# protoplank.net
KiCad netlist of a schematic drawn in EAGLE
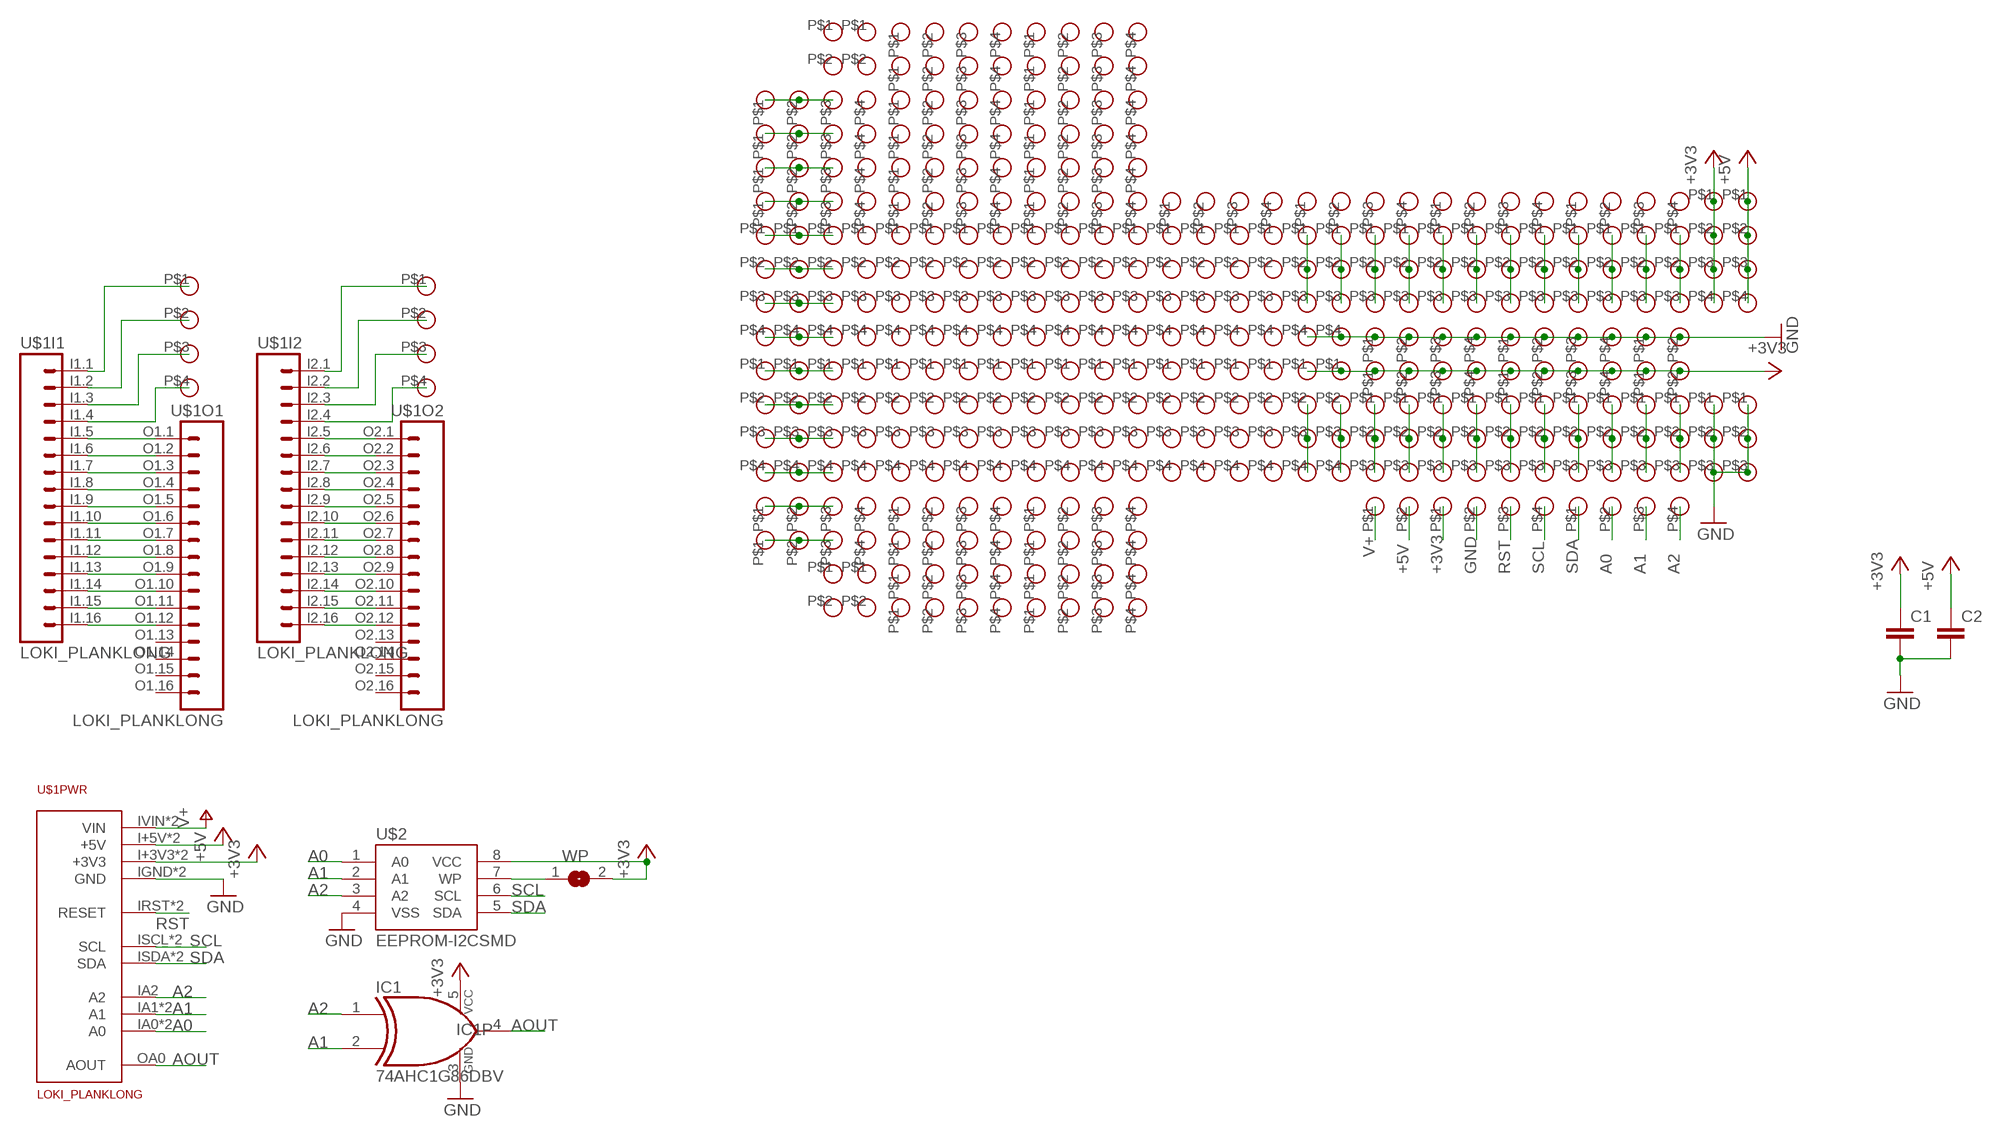
[diagram p0: schematic, sheet 1]

(export (version "E")
  (design (tool "Eeschema 10.0.6"))
  (components
    (comp (ref "C1")
      (value "CAPPTH")
      (footprint "eagle-import:CAP-PTH-SMALL")
      (libsource (lib "eagle-import") (part "CAPPTH"))
    )
    (comp (ref "C2")
      (value "CAPPTH")
      (footprint "eagle-import:CAP-PTH-SMALL")
      (libsource (lib "eagle-import") (part "CAPPTH"))
    )
    (comp (ref "IC1")
      (value "74AHC1G86DBV")
      (footprint "eagle-import:SOT23-5")
      (libsource (lib "eagle-import") (part "741G86DBVAHC"))
    )
    (comp (ref "U$1")
      (value "LOKI_PLANKLONG")
      (footprint "eagle-import:PLANK_LONG")
      (libsource (lib "eagle-import") (part "LOKI_PLANKLONG"))
    )
    (comp (ref "U$2")
      (value "EEPROM-I2CSMD")
      (footprint "eagle-import:SO08")
      (libsource (lib "eagle-import") (part "EEPROM-I2CSMD"))
    )
    (comp (ref "U$3")
      (value "PROTOPAD-3")
      (footprint "eagle-import:PROTOPAD-3")
      (libsource (lib "eagle-import") (part "PROTOPAD-3"))
    )
    (comp (ref "U$4")
      (value "PROTOPAD-3")
      (footprint "eagle-import:PROTOPAD-3")
      (libsource (lib "eagle-import") (part "PROTOPAD-3"))
    )
    (comp (ref "U$5")
      (value "PROTOPAD-3")
      (footprint "eagle-import:PROTOPAD-3")
      (libsource (lib "eagle-import") (part "PROTOPAD-3"))
    )
    (comp (ref "U$6")
      (value "PROTOPAD-3")
      (footprint "eagle-import:PROTOPAD-3")
      (libsource (lib "eagle-import") (part "PROTOPAD-3"))
    )
    (comp (ref "U$7")
      (value "PROTOPAD-3")
      (footprint "eagle-import:PROTOPAD-3")
      (libsource (lib "eagle-import") (part "PROTOPAD-3"))
    )
    (comp (ref "U$8")
      (value "PROTOPAD-3")
      (footprint "eagle-import:PROTOPAD-3")
      (libsource (lib "eagle-import") (part "PROTOPAD-3"))
    )
    (comp (ref "U$9")
      (value "PROTOPAD-3")
      (footprint "eagle-import:PROTOPAD-3")
      (libsource (lib "eagle-import") (part "PROTOPAD-3"))
    )
    (comp (ref "U$10")
      (value "PROTOPAD-3")
      (footprint "eagle-import:PROTOPAD-3")
      (libsource (lib "eagle-import") (part "PROTOPAD-3"))
    )
    (comp (ref "U$11")
      (value "PROTOPAD-3")
      (footprint "eagle-import:PROTOPAD-3")
      (libsource (lib "eagle-import") (part "PROTOPAD-3"))
    )
    (comp (ref "U$12")
      (value "PROTOPAD-3")
      (footprint "eagle-import:PROTOPAD-3")
      (libsource (lib "eagle-import") (part "PROTOPAD-3"))
    )
    (comp (ref "U$13")
      (value "PROTOPAD-3")
      (footprint "eagle-import:PROTOPAD-3")
      (libsource (lib "eagle-import") (part "PROTOPAD-3"))
    )
    (comp (ref "U$14")
      (value "PROTOPAD-3")
      (footprint "eagle-import:PROTOPAD-3")
      (libsource (lib "eagle-import") (part "PROTOPAD-3"))
    )
    (comp (ref "U$15")
      (value "PROTOPAD-3")
      (footprint "eagle-import:PROTOPAD-3")
      (libsource (lib "eagle-import") (part "PROTOPAD-3"))
    )
    (comp (ref "U$16")
      (value "PROTOPAD-3")
      (footprint "eagle-import:PROTOPAD-3")
      (libsource (lib "eagle-import") (part "PROTOPAD-3"))
    )
    (comp (ref "U$17")
      (value "PROTOPAD-3")
      (footprint "eagle-import:PROTOPAD-3")
      (libsource (lib "eagle-import") (part "PROTOPAD-3"))
    )
    (comp (ref "U$18")
      (value "PROTOPAD-3")
      (footprint "eagle-import:PROTOPAD-3")
      (libsource (lib "eagle-import") (part "PROTOPAD-3"))
    )
    (comp (ref "U$19")
      (value "PROTOPAD-3")
      (footprint "eagle-import:PROTOPAD-3")
      (libsource (lib "eagle-import") (part "PROTOPAD-3"))
    )
    (comp (ref "U$20")
      (value "PROTOPAD-3")
      (footprint "eagle-import:PROTOPAD-3")
      (libsource (lib "eagle-import") (part "PROTOPAD-3"))
    )
    (comp (ref "U$21")
      (value "PROTOPAD-3")
      (footprint "eagle-import:PROTOPAD-3")
      (libsource (lib "eagle-import") (part "PROTOPAD-3"))
    )
    (comp (ref "U$22")
      (value "PROTOPAD-3")
      (footprint "eagle-import:PROTOPAD-3")
      (libsource (lib "eagle-import") (part "PROTOPAD-3"))
    )
    (comp (ref "U$23")
      (value "PROTOPAD-4SQUARE")
      (footprint "eagle-import:PROTOPAD-4")
      (libsource (lib "eagle-import") (part "PROTOPAD-4SQUARE"))
    )
    (comp (ref "U$24")
      (value "PROTOPAD-4SQUARE")
      (footprint "eagle-import:PROTOPAD-4")
      (libsource (lib "eagle-import") (part "PROTOPAD-4SQUARE"))
    )
    (comp (ref "U$25")
      (value "PROTOPAD-4SQUARE")
      (footprint "eagle-import:PROTOPAD-4")
      (libsource (lib "eagle-import") (part "PROTOPAD-4SQUARE"))
    )
    (comp (ref "U$26")
      (value "PROTOPAD-4SQUARE")
      (footprint "eagle-import:PROTOPAD-4")
      (libsource (lib "eagle-import") (part "PROTOPAD-4SQUARE"))
    )
    (comp (ref "U$27")
      (value "PROTOPAD-2SQUARE")
      (footprint "eagle-import:PROTOPAD-2")
      (libsource (lib "eagle-import") (part "PROTOPAD-2SQUARE"))
    )
    (comp (ref "U$28")
      (value "PROTOPAD-2SQUARE")
      (footprint "eagle-import:PROTOPAD-2")
      (libsource (lib "eagle-import") (part "PROTOPAD-2SQUARE"))
    )
    (comp (ref "U$29")
      (value "PROTOPAD-4ROUND")
      (footprint "eagle-import:PROTOPAD-4-ROUND")
      (libsource (lib "eagle-import") (part "PROTOPAD-4ROUND"))
    )
    (comp (ref "U$30")
      (value "PROTOPAD-4ROUND")
      (footprint "eagle-import:PROTOPAD-4-ROUND")
      (libsource (lib "eagle-import") (part "PROTOPAD-4ROUND"))
    )
    (comp (ref "U$31")
      (value "PROTOPAD-4ROUND")
      (footprint "eagle-import:PROTOPAD-4-ROUND")
      (libsource (lib "eagle-import") (part "PROTOPAD-4ROUND"))
    )
    (comp (ref "U$32")
      (value "PROTOPAD-4ROUND")
      (footprint "eagle-import:PROTOPAD-4-ROUND")
      (libsource (lib "eagle-import") (part "PROTOPAD-4ROUND"))
    )
    (comp (ref "U$33")
      (value "PROTOPAD-2ROUND")
      (footprint "eagle-import:PROTOPAD-2-ROUND")
      (libsource (lib "eagle-import") (part "PROTOPAD-2ROUND"))
    )
    (comp (ref "U$34")
      (value "PROTOPAD-4SQUARE")
      (footprint "eagle-import:PROTOPAD-4")
      (libsource (lib "eagle-import") (part "PROTOPAD-4SQUARE"))
    )
    (comp (ref "U$35")
      (value "PROTOPAD-4SQUARE")
      (footprint "eagle-import:PROTOPAD-4")
      (libsource (lib "eagle-import") (part "PROTOPAD-4SQUARE"))
    )
    (comp (ref "U$36")
      (value "PROTOPAD-4SQUARE")
      (footprint "eagle-import:PROTOPAD-4")
      (libsource (lib "eagle-import") (part "PROTOPAD-4SQUARE"))
    )
    (comp (ref "U$37")
      (value "PROTOPAD-4SQUARE")
      (footprint "eagle-import:PROTOPAD-4")
      (libsource (lib "eagle-import") (part "PROTOPAD-4SQUARE"))
    )
    (comp (ref "U$38")
      (value "PROTOPAD-4SQUARE")
      (footprint "eagle-import:PROTOPAD-4")
      (libsource (lib "eagle-import") (part "PROTOPAD-4SQUARE"))
    )
    (comp (ref "U$39")
      (value "PROTOPAD-4SQUARE")
      (footprint "eagle-import:PROTOPAD-4")
      (libsource (lib "eagle-import") (part "PROTOPAD-4SQUARE"))
    )
    (comp (ref "U$40")
      (value "PROTOPAD-4SQUARE")
      (footprint "eagle-import:PROTOPAD-4")
      (libsource (lib "eagle-import") (part "PROTOPAD-4SQUARE"))
    )
    (comp (ref "U$41")
      (value "PROTOPAD-4SQUARE")
      (footprint "eagle-import:PROTOPAD-4")
      (libsource (lib "eagle-import") (part "PROTOPAD-4SQUARE"))
    )
    (comp (ref "U$42")
      (value "PROTOPAD-4SQUARE")
      (footprint "eagle-import:PROTOPAD-4")
      (libsource (lib "eagle-import") (part "PROTOPAD-4SQUARE"))
    )
    (comp (ref "U$43")
      (value "PROTOPAD-4SQUARE")
      (footprint "eagle-import:PROTOPAD-4")
      (libsource (lib "eagle-import") (part "PROTOPAD-4SQUARE"))
    )
    (comp (ref "U$44")
      (value "PROTOPAD-4SQUARE")
      (footprint "eagle-import:PROTOPAD-4")
      (libsource (lib "eagle-import") (part "PROTOPAD-4SQUARE"))
    )
    (comp (ref "U$45")
      (value "PROTOPAD-4SQUARE")
      (footprint "eagle-import:PROTOPAD-4")
      (libsource (lib "eagle-import") (part "PROTOPAD-4SQUARE"))
    )
    (comp (ref "U$46")
      (value "PROTOPAD-4SQUARE")
      (footprint "eagle-import:PROTOPAD-4")
      (libsource (lib "eagle-import") (part "PROTOPAD-4SQUARE"))
    )
    (comp (ref "U$47")
      (value "PROTOPAD-4SQUARE")
      (footprint "eagle-import:PROTOPAD-4")
      (libsource (lib "eagle-import") (part "PROTOPAD-4SQUARE"))
    )
    (comp (ref "U$48")
      (value "PROTOPAD-4SQUARE")
      (footprint "eagle-import:PROTOPAD-4")
      (libsource (lib "eagle-import") (part "PROTOPAD-4SQUARE"))
    )
    (comp (ref "U$49")
      (value "PROTOPAD-4SQUARE")
      (footprint "eagle-import:PROTOPAD-4")
      (libsource (lib "eagle-import") (part "PROTOPAD-4SQUARE"))
    )
    (comp (ref "U$50")
      (value "PROTOPAD-4SQUARE")
      (footprint "eagle-import:PROTOPAD-4")
      (libsource (lib "eagle-import") (part "PROTOPAD-4SQUARE"))
    )
    (comp (ref "U$51")
      (value "PROTOPAD-4SQUARE")
      (footprint "eagle-import:PROTOPAD-4")
      (libsource (lib "eagle-import") (part "PROTOPAD-4SQUARE"))
    )
    (comp (ref "U$52")
      (value "PROTOPAD-4SQUARE")
      (footprint "eagle-import:PROTOPAD-4")
      (libsource (lib "eagle-import") (part "PROTOPAD-4SQUARE"))
    )
    (comp (ref "U$53")
      (value "PROTOPAD-4SQUARE")
      (footprint "eagle-import:PROTOPAD-4")
      (libsource (lib "eagle-import") (part "PROTOPAD-4SQUARE"))
    )
    (comp (ref "U$54")
      (value "PROTOPAD-4SQUARE")
      (footprint "eagle-import:PROTOPAD-4")
      (libsource (lib "eagle-import") (part "PROTOPAD-4SQUARE"))
    )
    (comp (ref "U$55")
      (value "PROTOPAD-4SQUARE")
      (footprint "eagle-import:PROTOPAD-4")
      (libsource (lib "eagle-import") (part "PROTOPAD-4SQUARE"))
    )
    (comp (ref "U$56")
      (value "PROTOPAD-4SQUARE")
      (footprint "eagle-import:PROTOPAD-4")
      (libsource (lib "eagle-import") (part "PROTOPAD-4SQUARE"))
    )
    (comp (ref "U$57")
      (value "PROTOPAD-4SQUARE")
      (footprint "eagle-import:PROTOPAD-4")
      (libsource (lib "eagle-import") (part "PROTOPAD-4SQUARE"))
    )
    (comp (ref "U$58")
      (value "PROTOPAD-4SQUARE")
      (footprint "eagle-import:PROTOPAD-4")
      (libsource (lib "eagle-import") (part "PROTOPAD-4SQUARE"))
    )
    (comp (ref "U$59")
      (value "PROTOPAD-4SQUARE")
      (footprint "eagle-import:PROTOPAD-4")
      (libsource (lib "eagle-import") (part "PROTOPAD-4SQUARE"))
    )
    (comp (ref "U$60")
      (value "PROTOPAD-4SQUARE")
      (footprint "eagle-import:PROTOPAD-4")
      (libsource (lib "eagle-import") (part "PROTOPAD-4SQUARE"))
    )
    (comp (ref "U$61")
      (value "PROTOPAD-4SQUARE")
      (footprint "eagle-import:PROTOPAD-4")
      (libsource (lib "eagle-import") (part "PROTOPAD-4SQUARE"))
    )
    (comp (ref "U$62")
      (value "PROTOPAD-4SQUARE")
      (footprint "eagle-import:PROTOPAD-4")
      (libsource (lib "eagle-import") (part "PROTOPAD-4SQUARE"))
    )
    (comp (ref "U$63")
      (value "PROTOPAD-4SQUARE")
      (footprint "eagle-import:PROTOPAD-4")
      (libsource (lib "eagle-import") (part "PROTOPAD-4SQUARE"))
    )
    (comp (ref "U$64")
      (value "PROTOPAD-4SQUARE")
      (footprint "eagle-import:PROTOPAD-4")
      (libsource (lib "eagle-import") (part "PROTOPAD-4SQUARE"))
    )
    (comp (ref "U$65")
      (value "PROTOPAD-4SQUARE")
      (footprint "eagle-import:PROTOPAD-4")
      (libsource (lib "eagle-import") (part "PROTOPAD-4SQUARE"))
    )
    (comp (ref "U$66")
      (value "PROTOPAD-4SQUARE")
      (footprint "eagle-import:PROTOPAD-4")
      (libsource (lib "eagle-import") (part "PROTOPAD-4SQUARE"))
    )
    (comp (ref "U$67")
      (value "PROTOPAD-4SQUARE")
      (footprint "eagle-import:PROTOPAD-4")
      (libsource (lib "eagle-import") (part "PROTOPAD-4SQUARE"))
    )
    (comp (ref "U$68")
      (value "PROTOPAD-4SQUARE")
      (footprint "eagle-import:PROTOPAD-4")
      (libsource (lib "eagle-import") (part "PROTOPAD-4SQUARE"))
    )
    (comp (ref "U$69")
      (value "PROTOPAD-4SQUARE")
      (footprint "eagle-import:PROTOPAD-4")
      (libsource (lib "eagle-import") (part "PROTOPAD-4SQUARE"))
    )
    (comp (ref "U$70")
      (value "PROTOPAD-4SQUARE")
      (footprint "eagle-import:PROTOPAD-4")
      (libsource (lib "eagle-import") (part "PROTOPAD-4SQUARE"))
    )
    (comp (ref "U$71")
      (value "PROTOPAD-4SQUARE")
      (footprint "eagle-import:PROTOPAD-4")
      (libsource (lib "eagle-import") (part "PROTOPAD-4SQUARE"))
    )
    (comp (ref "U$72")
      (value "PROTOPAD-4SQUARE")
      (footprint "eagle-import:PROTOPAD-4")
      (libsource (lib "eagle-import") (part "PROTOPAD-4SQUARE"))
    )
    (comp (ref "U$73")
      (value "PROTOPAD-4SQUARE")
      (footprint "eagle-import:PROTOPAD-4")
      (libsource (lib "eagle-import") (part "PROTOPAD-4SQUARE"))
    )
    (comp (ref "U$74")
      (value "PROTOPAD-4SQUARE")
      (footprint "eagle-import:PROTOPAD-4")
      (libsource (lib "eagle-import") (part "PROTOPAD-4SQUARE"))
    )
    (comp (ref "U$75")
      (value "PROTOPAD-4SQUARE")
      (footprint "eagle-import:PROTOPAD-4")
      (libsource (lib "eagle-import") (part "PROTOPAD-4SQUARE"))
    )
    (comp (ref "U$76")
      (value "PROTOPAD-4SQUARE")
      (footprint "eagle-import:PROTOPAD-4")
      (libsource (lib "eagle-import") (part "PROTOPAD-4SQUARE"))
    )
    (comp (ref "U$77")
      (value "PROTOPAD-4SQUARE")
      (footprint "eagle-import:PROTOPAD-4")
      (libsource (lib "eagle-import") (part "PROTOPAD-4SQUARE"))
    )
    (comp (ref "U$78")
      (value "PROTOPAD-3")
      (footprint "eagle-import:PROTOPAD-3")
      (libsource (lib "eagle-import") (part "PROTOPAD-3"))
    )
    (comp (ref "U$79")
      (value "PROTOPAD-4SQUARE")
      (footprint "eagle-import:PROTOPAD-4")
      (libsource (lib "eagle-import") (part "PROTOPAD-4SQUARE"))
    )
    (comp (ref "U$80")
      (value "PROTOPAD-3")
      (footprint "eagle-import:PROTOPAD-3")
      (libsource (lib "eagle-import") (part "PROTOPAD-3"))
    )
    (comp (ref "U$81")
      (value "PROTOPAD-4SQUARE")
      (footprint "eagle-import:PROTOPAD-4")
      (libsource (lib "eagle-import") (part "PROTOPAD-4SQUARE"))
    )
    (comp (ref "U$82")
      (value "PROTOPAD-4SQUARE")
      (footprint "eagle-import:PROTOPAD-4")
      (libsource (lib "eagle-import") (part "PROTOPAD-4SQUARE"))
    )
    (comp (ref "U$83")
      (value "PROTOPAD-4SQUARE")
      (footprint "eagle-import:PROTOPAD-4")
      (libsource (lib "eagle-import") (part "PROTOPAD-4SQUARE"))
    )
    (comp (ref "U$84")
      (value "PROTOPAD-4SQUARE")
      (footprint "eagle-import:PROTOPAD-4")
      (libsource (lib "eagle-import") (part "PROTOPAD-4SQUARE"))
    )
    (comp (ref "U$85")
      (value "PROTOPAD-4SQUARE")
      (footprint "eagle-import:PROTOPAD-4")
      (libsource (lib "eagle-import") (part "PROTOPAD-4SQUARE"))
    )
    (comp (ref "U$86")
      (value "PROTOPAD-4SQUARE")
      (footprint "eagle-import:PROTOPAD-4")
      (libsource (lib "eagle-import") (part "PROTOPAD-4SQUARE"))
    )
    (comp (ref "U$87")
      (value "PROTOPAD-4SQUARE")
      (footprint "eagle-import:PROTOPAD-4")
      (libsource (lib "eagle-import") (part "PROTOPAD-4SQUARE"))
    )
    (comp (ref "U$88")
      (value "PROTOPAD-4SQUARE")
      (footprint "eagle-import:PROTOPAD-4")
      (libsource (lib "eagle-import") (part "PROTOPAD-4SQUARE"))
    )
    (comp (ref "U$89")
      (value "PROTOPAD-4SQUARE")
      (footprint "eagle-import:PROTOPAD-4")
      (libsource (lib "eagle-import") (part "PROTOPAD-4SQUARE"))
    )
    (comp (ref "U$90")
      (value "PROTOPAD-4SQUARE")
      (footprint "eagle-import:PROTOPAD-4")
      (libsource (lib "eagle-import") (part "PROTOPAD-4SQUARE"))
    )
    (comp (ref "U$91")
      (value "PROTOPAD-4SQUARE")
      (footprint "eagle-import:PROTOPAD-4")
      (libsource (lib "eagle-import") (part "PROTOPAD-4SQUARE"))
    )
    (comp (ref "U$92")
      (value "PROTOPAD-4SQUARE")
      (footprint "eagle-import:PROTOPAD-4")
      (libsource (lib "eagle-import") (part "PROTOPAD-4SQUARE"))
    )
    (comp (ref "U$93")
      (value "PROTOPAD-4SQUARE")
      (footprint "eagle-import:PROTOPAD-4")
      (libsource (lib "eagle-import") (part "PROTOPAD-4SQUARE"))
    )
    (comp (ref "U$94")
      (value "PROTOPAD-4SQUARE")
      (footprint "eagle-import:PROTOPAD-4")
      (libsource (lib "eagle-import") (part "PROTOPAD-4SQUARE"))
    )
    (comp (ref "U$95")
      (value "PROTOPAD-4SQUARE")
      (footprint "eagle-import:PROTOPAD-4")
      (libsource (lib "eagle-import") (part "PROTOPAD-4SQUARE"))
    )
    (comp (ref "U$96")
      (value "PROTOPAD-4SQUARE")
      (footprint "eagle-import:PROTOPAD-4")
      (libsource (lib "eagle-import") (part "PROTOPAD-4SQUARE"))
    )
    (comp (ref "U$97")
      (value "PROTOPAD-4SQUARE")
      (footprint "eagle-import:PROTOPAD-4")
      (libsource (lib "eagle-import") (part "PROTOPAD-4SQUARE"))
    )
    (comp (ref "U$98")
      (value "PROTOPAD-4SQUARE")
      (footprint "eagle-import:PROTOPAD-4")
      (libsource (lib "eagle-import") (part "PROTOPAD-4SQUARE"))
    )
    (comp (ref "U$99")
      (value "PROTOPAD-4SQUARE")
      (footprint "eagle-import:PROTOPAD-4")
      (libsource (lib "eagle-import") (part "PROTOPAD-4SQUARE"))
    )
    (comp (ref "U$100")
      (value "PROTOPAD-4SQUARE")
      (footprint "eagle-import:PROTOPAD-4")
      (libsource (lib "eagle-import") (part "PROTOPAD-4SQUARE"))
    )
    (comp (ref "U$101")
      (value "PROTOPAD-4SQUARE")
      (footprint "eagle-import:PROTOPAD-4")
      (libsource (lib "eagle-import") (part "PROTOPAD-4SQUARE"))
    )
    (comp (ref "U$102")
      (value "PROTOPAD-4SQUARE")
      (footprint "eagle-import:PROTOPAD-4")
      (libsource (lib "eagle-import") (part "PROTOPAD-4SQUARE"))
    )
    (comp (ref "U$103")
      (value "PROTOPAD-4SQUARE")
      (footprint "eagle-import:PROTOPAD-4")
      (libsource (lib "eagle-import") (part "PROTOPAD-4SQUARE"))
    )
    (comp (ref "U$104")
      (value "PROTOPAD-2SQUARE")
      (footprint "eagle-import:PROTOPAD-2")
      (libsource (lib "eagle-import") (part "PROTOPAD-2SQUARE"))
    )
    (comp (ref "U$105")
      (value "PROTOPAD-2SQUARE")
      (footprint "eagle-import:PROTOPAD-2")
      (libsource (lib "eagle-import") (part "PROTOPAD-2SQUARE"))
    )
    (comp (ref "U$106")
      (value "PROTOPAD-2SQUARE")
      (footprint "eagle-import:PROTOPAD-2")
      (libsource (lib "eagle-import") (part "PROTOPAD-2SQUARE"))
    )
    (comp (ref "U$107")
      (value "PROTOPAD-2SQUARE")
      (footprint "eagle-import:PROTOPAD-2")
      (libsource (lib "eagle-import") (part "PROTOPAD-2SQUARE"))
    )
    (comp (ref "WP") (value "SJ") (footprint "eagle-import:SJ") (libsource (lib "eagle-import") (part "SJ")))
  )
  (nets
    (net (code "1") (name "+3V3") (class "Default")
      (node (ref "C1") (pin "1") (pinfunction "1_1") (pintype "passive"))
      (node (ref "IC1") (pin "5") (pinfunction "VCC_5") (pintype "power_in"))
      (node (ref "U$1") (pin "I+3V3") (pinfunction "+3V3_I+3V3") (pintype "power_in"))
      (node (ref "U$1") (pin "O+3V3") (pinfunction "+3V3_O+3V3") (pintype "power_in"))
      (node (ref "U$2") (pin "8") (pinfunction "VCC_8") (pintype "power_in"))
      (node (ref "U$25") (pin "P$1") (pinfunction "P$1_P$1") (pintype "passive"))
      (node (ref "U$25") (pin "P$2") (pinfunction "P$2_P$2") (pintype "passive"))
      (node (ref "U$25") (pin "P$3") (pinfunction "P$3_P$3") (pintype "passive"))
      (node (ref "U$25") (pin "P$4") (pinfunction "P$4_P$4") (pintype "passive"))
      (node (ref "U$26") (pin "P$1") (pinfunction "P$1_P$1") (pintype "passive"))
      (node (ref "U$26") (pin "P$2") (pinfunction "P$2_P$2") (pintype "passive"))
      (node (ref "U$26") (pin "P$3") (pinfunction "P$3_P$3") (pintype "passive"))
      (node (ref "U$26") (pin "P$4") (pinfunction "P$4_P$4") (pintype "passive"))
      (node (ref "U$28") (pin "P$1") (pinfunction "P$1_P$1") (pintype "passive"))
      (node (ref "U$28") (pin "P$2") (pinfunction "P$2_P$2") (pintype "passive"))
      (node (ref "U$32") (pin "P$1") (pinfunction "P$1_P$1") (pintype "passive"))
      (node (ref "U$35") (pin "P$1") (pinfunction "P$1_P$1") (pintype "passive"))
      (node (ref "U$36") (pin "P$1") (pinfunction "P$1_P$1") (pintype "passive"))
      (node (ref "U$77") (pin "P$1") (pinfunction "P$1_P$1") (pintype "passive"))
      (node (ref "U$77") (pin "P$2") (pinfunction "P$2_P$2") (pintype "passive"))
      (node (ref "U$77") (pin "P$3") (pinfunction "P$3_P$3") (pintype "passive"))
      (node (ref "U$77") (pin "P$4") (pinfunction "P$4_P$4") (pintype "passive"))
      (node (ref "WP") (pin "2") (pinfunction "2_2") (pintype "passive"))
    )
    (net (code "2") (name "+5V") (class "Default")
      (node (ref "C2") (pin "1") (pinfunction "1_1") (pintype "passive"))
      (node (ref "U$1") (pin "I+5V") (pinfunction "+5V_I+5V") (pintype "power_in"))
      (node (ref "U$1") (pin "O+5V") (pinfunction "+5V_O+5V") (pintype "power_in"))
      (node (ref "U$33") (pin "P$2") (pinfunction "P$2_P$2") (pintype "passive"))
      (node (ref "U$79") (pin "P$1") (pinfunction "P$1_P$1") (pintype "passive"))
      (node (ref "U$79") (pin "P$2") (pinfunction "P$2_P$2") (pintype "passive"))
      (node (ref "U$79") (pin "P$3") (pinfunction "P$3_P$3") (pintype "passive"))
      (node (ref "U$79") (pin "P$4") (pinfunction "P$4_P$4") (pintype "passive"))
    )
    (net (code "3") (name "/A0") (class "Default")
      (node (ref "U$1") (pin "IA0") (pinfunction "A0_IA0") (pintype "output"))
      (node (ref "U$1") (pin "OA1") (pinfunction "A0_OA1") (pintype "output"))
      (node (ref "U$2") (pin "1") (pinfunction "A0_1") (pintype "bidirectional"))
      (node (ref "U$31") (pin "P$2") (pinfunction "P$2_P$2") (pintype "passive"))
    )
    (net (code "4") (name "/A1") (class "Default")
      (node (ref "IC1") (pin "2") (pinfunction "I1_2") (pintype "input"))
      (node (ref "U$1") (pin "IA1") (pinfunction "A1_IA1") (pintype "output"))
      (node (ref "U$1") (pin "OA2") (pinfunction "A1_OA2") (pintype "output"))
      (node (ref "U$2") (pin "2") (pinfunction "A1_2") (pintype "bidirectional"))
      (node (ref "U$31") (pin "P$3") (pinfunction "P$3_P$3") (pintype "passive"))
    )
    (net (code "5") (name "/A2") (class "Default")
      (node (ref "IC1") (pin "1") (pinfunction "I0_1") (pintype "input"))
      (node (ref "U$1") (pin "IA2") (pinfunction "A2_IA2") (pintype "output"))
      (node (ref "U$2") (pin "3") (pinfunction "A2_3") (pintype "bidirectional"))
      (node (ref "U$31") (pin "P$4") (pinfunction "P$4_P$4") (pintype "passive"))
    )
    (net (code "6") (name "/AOUT") (class "Default")
      (node (ref "IC1") (pin "4") (pinfunction "O_4") (pintype "output"))
      (node (ref "U$1") (pin "OA0") (pinfunction "AOUT_OA0") (pintype "input"))
    )
    (net (code "7") (name "/RST") (class "Default")
      (node (ref "U$1") (pin "IRST") (pinfunction "RESET_IRST") (pintype "input"))
      (node (ref "U$1") (pin "ORST") (pinfunction "RESET_ORST") (pintype "input"))
      (node (ref "U$32") (pin "P$3") (pinfunction "P$3_P$3") (pintype "passive"))
    )
    (net (code "8") (name "/SCL") (class "Default")
      (node (ref "U$1") (pin "ISCL") (pinfunction "SCL_ISCL") (pintype "bidirectional"))
      (node (ref "U$1") (pin "OSCL") (pinfunction "SCL_OSCL") (pintype "bidirectional"))
      (node (ref "U$2") (pin "6") (pinfunction "SCL_6") (pintype "bidirectional"))
      (node (ref "U$32") (pin "P$4") (pinfunction "P$4_P$4") (pintype "passive"))
    )
    (net (code "9") (name "/SDA") (class "Default")
      (node (ref "U$1") (pin "ISDA") (pinfunction "SDA_ISDA") (pintype "bidirectional"))
      (node (ref "U$1") (pin "OSDA") (pinfunction "SDA_OSDA") (pintype "bidirectional"))
      (node (ref "U$2") (pin "5") (pinfunction "SDA_5") (pintype "bidirectional"))
      (node (ref "U$31") (pin "P$1") (pinfunction "P$1_P$1") (pintype "passive"))
    )
    (net (code "10") (name "GND") (class "Default")
      (node (ref "C1") (pin "2") (pinfunction "2_2") (pintype "passive"))
      (node (ref "C2") (pin "2") (pinfunction "2_2") (pintype "passive"))
      (node (ref "IC1") (pin "3") (pinfunction "GND_3") (pintype "power_in"))
      (node (ref "U$1") (pin "IGND") (pinfunction "GND_IGND") (pintype "power_in"))
      (node (ref "U$1") (pin "OGND") (pinfunction "GND_OGND") (pintype "power_in"))
      (node (ref "U$2") (pin "4") (pinfunction "VSS_4") (pintype "power_in"))
      (node (ref "U$23") (pin "P$1") (pinfunction "P$1_P$1") (pintype "passive"))
      (node (ref "U$23") (pin "P$2") (pinfunction "P$2_P$2") (pintype "passive"))
      (node (ref "U$23") (pin "P$3") (pinfunction "P$3_P$3") (pintype "passive"))
      (node (ref "U$23") (pin "P$4") (pinfunction "P$4_P$4") (pintype "passive"))
      (node (ref "U$24") (pin "P$1") (pinfunction "P$1_P$1") (pintype "passive"))
      (node (ref "U$24") (pin "P$2") (pinfunction "P$2_P$2") (pintype "passive"))
      (node (ref "U$24") (pin "P$3") (pinfunction "P$3_P$3") (pintype "passive"))
      (node (ref "U$24") (pin "P$4") (pinfunction "P$4_P$4") (pintype "passive"))
      (node (ref "U$27") (pin "P$1") (pinfunction "P$1_P$1") (pintype "passive"))
      (node (ref "U$27") (pin "P$2") (pinfunction "P$2_P$2") (pintype "passive"))
      (node (ref "U$32") (pin "P$2") (pinfunction "P$2_P$2") (pintype "passive"))
      (node (ref "U$34") (pin "P$4") (pinfunction "P$4_P$4") (pintype "passive"))
      (node (ref "U$37") (pin "P$4") (pinfunction "P$4_P$4") (pintype "passive"))
      (node (ref "U$78") (pin "P$1") (pinfunction "P$1_P$1") (pintype "passive"))
      (node (ref "U$78") (pin "P$2") (pinfunction "P$2_P$2") (pintype "passive"))
      (node (ref "U$78") (pin "P$3") (pinfunction "P$3_P$3") (pintype "passive"))
      (node (ref "U$80") (pin "P$1") (pinfunction "P$1_P$1") (pintype "passive"))
      (node (ref "U$80") (pin "P$2") (pinfunction "P$2_P$2") (pintype "passive"))
      (node (ref "U$80") (pin "P$3") (pinfunction "P$3_P$3") (pintype "passive"))
    )
    (net (code "11") (name "Net-(U$1A-1)") (class "Default")
      (node (ref "U$1") (pin "I1.1") (pinfunction "1_I1.1") (pintype "passive"))
      (node (ref "U$29") (pin "P$1") (pinfunction "P$1_P$1") (pintype "passive"))
    )
    (net (code "12") (name "Net-(U$1A-2)") (class "Default")
      (node (ref "U$1") (pin "I1.2") (pinfunction "2_I1.2") (pintype "passive"))
      (node (ref "U$29") (pin "P$2") (pinfunction "P$2_P$2") (pintype "passive"))
    )
    (net (code "13") (name "Net-(U$1A-3)") (class "Default")
      (node (ref "U$1") (pin "I1.3") (pinfunction "3_I1.3") (pintype "passive"))
      (node (ref "U$29") (pin "P$3") (pinfunction "P$3_P$3") (pintype "passive"))
    )
    (net (code "14") (name "Net-(U$1A-4)") (class "Default")
      (node (ref "U$1") (pin "I1.4") (pinfunction "4_I1.4") (pintype "passive"))
      (node (ref "U$29") (pin "P$4") (pinfunction "P$4_P$4") (pintype "passive"))
    )
    (net (code "15") (name "Net-(U$1A-5)") (class "Default")
      (node (ref "U$1") (pin "I1.5") (pinfunction "5_I1.5") (pintype "passive"))
      (node (ref "U$1") (pin "O1.1") (pinfunction "1_O1.1") (pintype "passive"))
    )
    (net (code "16") (name "Net-(U$1A-6)") (class "Default")
      (node (ref "U$1") (pin "I1.6") (pinfunction "6_I1.6") (pintype "passive"))
      (node (ref "U$1") (pin "O1.2") (pinfunction "2_O1.2") (pintype "passive"))
    )
    (net (code "17") (name "Net-(U$1A-7)") (class "Default")
      (node (ref "U$1") (pin "I1.7") (pinfunction "7_I1.7") (pintype "passive"))
      (node (ref "U$1") (pin "O1.3") (pinfunction "3_O1.3") (pintype "passive"))
    )
    (net (code "18") (name "Net-(U$1A-8)") (class "Default")
      (node (ref "U$1") (pin "I1.8") (pinfunction "8_I1.8") (pintype "passive"))
      (node (ref "U$1") (pin "O1.4") (pinfunction "4_O1.4") (pintype "passive"))
    )
    (net (code "19") (name "Net-(U$1A-9)") (class "Default")
      (node (ref "U$1") (pin "I1.9") (pinfunction "9_I1.9") (pintype "passive"))
      (node (ref "U$1") (pin "O1.5") (pinfunction "5_O1.5") (pintype "passive"))
    )
    (net (code "20") (name "Net-(U$1A-10)") (class "Default")
      (node (ref "U$1") (pin "I1.10") (pinfunction "10_I1.10") (pintype "passive"))
      (node (ref "U$1") (pin "O1.6") (pinfunction "6_O1.6") (pintype "passive"))
    )
    (net (code "21") (name "Net-(U$1A-11)") (class "Default")
      (node (ref "U$1") (pin "I1.11") (pinfunction "11_I1.11") (pintype "passive"))
      (node (ref "U$1") (pin "O1.7") (pinfunction "7_O1.7") (pintype "passive"))
    )
    (net (code "22") (name "Net-(U$1A-12)") (class "Default")
      (node (ref "U$1") (pin "I1.12") (pinfunction "12_I1.12") (pintype "passive"))
      (node (ref "U$1") (pin "O1.8") (pinfunction "8_O1.8") (pintype "passive"))
    )
    (net (code "23") (name "Net-(U$1A-13)") (class "Default")
      (node (ref "U$1") (pin "I1.13") (pinfunction "13_I1.13") (pintype "passive"))
      (node (ref "U$1") (pin "O1.9") (pinfunction "9_O1.9") (pintype "passive"))
    )
    (net (code "24") (name "Net-(U$1A-14)") (class "Default")
      (node (ref "U$1") (pin "I1.14") (pinfunction "14_I1.14") (pintype "passive"))
      (node (ref "U$1") (pin "O1.10") (pinfunction "10_O1.10") (pintype "passive"))
    )
    (net (code "25") (name "Net-(U$1A-15)") (class "Default")
      (node (ref "U$1") (pin "I1.15") (pinfunction "15_I1.15") (pintype "passive"))
      (node (ref "U$1") (pin "O1.11") (pinfunction "11_O1.11") (pintype "passive"))
    )
    (net (code "26") (name "Net-(U$1A-16)") (class "Default")
      (node (ref "U$1") (pin "I1.16") (pinfunction "16_I1.16") (pintype "passive"))
      (node (ref "U$1") (pin "O1.12") (pinfunction "12_O1.12") (pintype "passive"))
    )
    (net (code "27") (name "Net-(U$1B-1)") (class "Default")
      (node (ref "U$1") (pin "I2.1") (pinfunction "1_I2.1") (pintype "passive"))
      (node (ref "U$30") (pin "P$1") (pinfunction "P$1_P$1") (pintype "passive"))
    )
    (net (code "28") (name "Net-(U$1B-2)") (class "Default")
      (node (ref "U$1") (pin "I2.2") (pinfunction "2_I2.2") (pintype "passive"))
      (node (ref "U$30") (pin "P$2") (pinfunction "P$2_P$2") (pintype "passive"))
    )
    (net (code "29") (name "Net-(U$1B-3)") (class "Default")
      (node (ref "U$1") (pin "I2.3") (pinfunction "3_I2.3") (pintype "passive"))
      (node (ref "U$30") (pin "P$3") (pinfunction "P$3_P$3") (pintype "passive"))
    )
    (net (code "30") (name "Net-(U$1B-4)") (class "Default")
      (node (ref "U$1") (pin "I2.4") (pinfunction "4_I2.4") (pintype "passive"))
      (node (ref "U$30") (pin "P$4") (pinfunction "P$4_P$4") (pintype "passive"))
    )
    (net (code "31") (name "Net-(U$1B-5)") (class "Default")
      (node (ref "U$1") (pin "I2.5") (pinfunction "5_I2.5") (pintype "passive"))
      (node (ref "U$1") (pin "O2.1") (pinfunction "1_O2.1") (pintype "passive"))
    )
    (net (code "32") (name "Net-(U$1B-6)") (class "Default")
      (node (ref "U$1") (pin "I2.6") (pinfunction "6_I2.6") (pintype "passive"))
      (node (ref "U$1") (pin "O2.2") (pinfunction "2_O2.2") (pintype "passive"))
    )
    (net (code "33") (name "Net-(U$1B-7)") (class "Default")
      (node (ref "U$1") (pin "I2.7") (pinfunction "7_I2.7") (pintype "passive"))
      (node (ref "U$1") (pin "O2.3") (pinfunction "3_O2.3") (pintype "passive"))
    )
    (net (code "34") (name "Net-(U$1B-8)") (class "Default")
      (node (ref "U$1") (pin "I2.8") (pinfunction "8_I2.8") (pintype "passive"))
      (node (ref "U$1") (pin "O2.4") (pinfunction "4_O2.4") (pintype "passive"))
    )
    (net (code "35") (name "Net-(U$1B-9)") (class "Default")
      (node (ref "U$1") (pin "I2.9") (pinfunction "9_I2.9") (pintype "passive"))
      (node (ref "U$1") (pin "O2.5") (pinfunction "5_O2.5") (pintype "passive"))
    )
    (net (code "36") (name "Net-(U$1B-10)") (class "Default")
      (node (ref "U$1") (pin "I2.10") (pinfunction "10_I2.10") (pintype "passive"))
      (node (ref "U$1") (pin "O2.6") (pinfunction "6_O2.6") (pintype "passive"))
    )
    (net (code "37") (name "Net-(U$1B-11)") (class "Default")
      (node (ref "U$1") (pin "I2.11") (pinfunction "11_I2.11") (pintype "passive"))
      (node (ref "U$1") (pin "O2.7") (pinfunction "7_O2.7") (pintype "passive"))
    )
    (net (code "38") (name "Net-(U$1B-12)") (class "Default")
      (node (ref "U$1") (pin "I2.12") (pinfunction "12_I2.12") (pintype "passive"))
      (node (ref "U$1") (pin "O2.8") (pinfunction "8_O2.8") (pintype "passive"))
    )
    (net (code "39") (name "Net-(U$1B-13)") (class "Default")
      (node (ref "U$1") (pin "I2.13") (pinfunction "13_I2.13") (pintype "passive"))
      (node (ref "U$1") (pin "O2.9") (pinfunction "9_O2.9") (pintype "passive"))
    )
    (net (code "40") (name "Net-(U$1B-14)") (class "Default")
      (node (ref "U$1") (pin "I2.14") (pinfunction "14_I2.14") (pintype "passive"))
      (node (ref "U$1") (pin "O2.10") (pinfunction "10_O2.10") (pintype "passive"))
    )
    (net (code "41") (name "Net-(U$1B-15)") (class "Default")
      (node (ref "U$1") (pin "I2.15") (pinfunction "15_I2.15") (pintype "passive"))
      (node (ref "U$1") (pin "O2.11") (pinfunction "11_O2.11") (pintype "passive"))
    )
    (net (code "42") (name "Net-(U$1B-16)") (class "Default")
      (node (ref "U$1") (pin "I2.16") (pinfunction "16_I2.16") (pintype "passive"))
      (node (ref "U$1") (pin "O2.12") (pinfunction "12_O2.12") (pintype "passive"))
    )
    (net (code "43") (name "Net-(U$2-WP)") (class "Default")
      (node (ref "U$2") (pin "7") (pinfunction "WP_7") (pintype "bidirectional"))
      (node (ref "WP") (pin "1") (pinfunction "1_1") (pintype "passive"))
    )
    (net (code "44") (name "Net-(U$3-PadP$1)") (class "Default")
      (node (ref "U$3") (pin "P$1") (pinfunction "P$1_P$1") (pintype "passive"))
      (node (ref "U$3") (pin "P$2") (pinfunction "P$2_P$2") (pintype "passive"))
      (node (ref "U$3") (pin "P$3") (pinfunction "P$3_P$3") (pintype "passive"))
    )
    (net (code "45") (name "Net-(U$4-PadP$1)") (class "Default")
      (node (ref "U$4") (pin "P$1") (pinfunction "P$1_P$1") (pintype "passive"))
      (node (ref "U$4") (pin "P$2") (pinfunction "P$2_P$2") (pintype "passive"))
      (node (ref "U$4") (pin "P$3") (pinfunction "P$3_P$3") (pintype "passive"))
    )
    (net (code "46") (name "Net-(U$5-PadP$1)") (class "Default")
      (node (ref "U$5") (pin "P$1") (pinfunction "P$1_P$1") (pintype "passive"))
      (node (ref "U$5") (pin "P$2") (pinfunction "P$2_P$2") (pintype "passive"))
      (node (ref "U$5") (pin "P$3") (pinfunction "P$3_P$3") (pintype "passive"))
    )
    (net (code "47") (name "Net-(U$6-PadP$1)") (class "Default")
      (node (ref "U$6") (pin "P$1") (pinfunction "P$1_P$1") (pintype "passive"))
      (node (ref "U$6") (pin "P$2") (pinfunction "P$2_P$2") (pintype "passive"))
      (node (ref "U$6") (pin "P$3") (pinfunction "P$3_P$3") (pintype "passive"))
    )
    (net (code "48") (name "Net-(U$7-PadP$1)") (class "Default")
      (node (ref "U$7") (pin "P$1") (pinfunction "P$1_P$1") (pintype "passive"))
      (node (ref "U$7") (pin "P$2") (pinfunction "P$2_P$2") (pintype "passive"))
      (node (ref "U$7") (pin "P$3") (pinfunction "P$3_P$3") (pintype "passive"))
    )
    (net (code "49") (name "Net-(U$8-PadP$1)") (class "Default")
      (node (ref "U$8") (pin "P$1") (pinfunction "P$1_P$1") (pintype "passive"))
      (node (ref "U$8") (pin "P$2") (pinfunction "P$2_P$2") (pintype "passive"))
      (node (ref "U$8") (pin "P$3") (pinfunction "P$3_P$3") (pintype "passive"))
    )
    (net (code "50") (name "Net-(U$9-PadP$1)") (class "Default")
      (node (ref "U$9") (pin "P$1") (pinfunction "P$1_P$1") (pintype "passive"))
      (node (ref "U$9") (pin "P$2") (pinfunction "P$2_P$2") (pintype "passive"))
      (node (ref "U$9") (pin "P$3") (pinfunction "P$3_P$3") (pintype "passive"))
    )
    (net (code "51") (name "Net-(U$10-PadP$1)") (class "Default")
      (node (ref "U$10") (pin "P$1") (pinfunction "P$1_P$1") (pintype "passive"))
      (node (ref "U$10") (pin "P$2") (pinfunction "P$2_P$2") (pintype "passive"))
      (node (ref "U$10") (pin "P$3") (pinfunction "P$3_P$3") (pintype "passive"))
    )
    (net (code "52") (name "Net-(U$11-PadP$1)") (class "Default")
      (node (ref "U$11") (pin "P$1") (pinfunction "P$1_P$1") (pintype "passive"))
      (node (ref "U$11") (pin "P$2") (pinfunction "P$2_P$2") (pintype "passive"))
      (node (ref "U$11") (pin "P$3") (pinfunction "P$3_P$3") (pintype "passive"))
    )
    (net (code "53") (name "Net-(U$12-PadP$1)") (class "Default")
      (node (ref "U$12") (pin "P$1") (pinfunction "P$1_P$1") (pintype "passive"))
      (node (ref "U$12") (pin "P$2") (pinfunction "P$2_P$2") (pintype "passive"))
      (node (ref "U$12") (pin "P$3") (pinfunction "P$3_P$3") (pintype "passive"))
    )
    (net (code "54") (name "Net-(U$13-PadP$1)") (class "Default")
      (node (ref "U$13") (pin "P$1") (pinfunction "P$1_P$1") (pintype "passive"))
      (node (ref "U$13") (pin "P$2") (pinfunction "P$2_P$2") (pintype "passive"))
      (node (ref "U$13") (pin "P$3") (pinfunction "P$3_P$3") (pintype "passive"))
    )
    (net (code "55") (name "Net-(U$14-PadP$1)") (class "Default")
      (node (ref "U$14") (pin "P$1") (pinfunction "P$1_P$1") (pintype "passive"))
      (node (ref "U$14") (pin "P$2") (pinfunction "P$2_P$2") (pintype "passive"))
      (node (ref "U$14") (pin "P$3") (pinfunction "P$3_P$3") (pintype "passive"))
    )
    (net (code "56") (name "Net-(U$15-PadP$1)") (class "Default")
      (node (ref "U$15") (pin "P$1") (pinfunction "P$1_P$1") (pintype "passive"))
      (node (ref "U$15") (pin "P$2") (pinfunction "P$2_P$2") (pintype "passive"))
      (node (ref "U$15") (pin "P$3") (pinfunction "P$3_P$3") (pintype "passive"))
    )
    (net (code "57") (name "Net-(U$16-PadP$1)") (class "Default")
      (node (ref "U$16") (pin "P$1") (pinfunction "P$1_P$1") (pintype "passive"))
      (node (ref "U$16") (pin "P$2") (pinfunction "P$2_P$2") (pintype "passive"))
      (node (ref "U$16") (pin "P$3") (pinfunction "P$3_P$3") (pintype "passive"))
    )
    (net (code "58") (name "Net-(U$17-PadP$1)") (class "Default")
      (node (ref "U$17") (pin "P$1") (pinfunction "P$1_P$1") (pintype "passive"))
      (node (ref "U$17") (pin "P$2") (pinfunction "P$2_P$2") (pintype "passive"))
      (node (ref "U$17") (pin "P$3") (pinfunction "P$3_P$3") (pintype "passive"))
    )
    (net (code "59") (name "Net-(U$18-PadP$1)") (class "Default")
      (node (ref "U$18") (pin "P$1") (pinfunction "P$1_P$1") (pintype "passive"))
      (node (ref "U$18") (pin "P$2") (pinfunction "P$2_P$2") (pintype "passive"))
      (node (ref "U$18") (pin "P$3") (pinfunction "P$3_P$3") (pintype "passive"))
    )
    (net (code "60") (name "Net-(U$19-PadP$1)") (class "Default")
      (node (ref "U$19") (pin "P$1") (pinfunction "P$1_P$1") (pintype "passive"))
      (node (ref "U$19") (pin "P$2") (pinfunction "P$2_P$2") (pintype "passive"))
      (node (ref "U$19") (pin "P$3") (pinfunction "P$3_P$3") (pintype "passive"))
    )
    (net (code "61") (name "Net-(U$20-PadP$1)") (class "Default")
      (node (ref "U$20") (pin "P$1") (pinfunction "P$1_P$1") (pintype "passive"))
      (node (ref "U$20") (pin "P$2") (pinfunction "P$2_P$2") (pintype "passive"))
      (node (ref "U$20") (pin "P$3") (pinfunction "P$3_P$3") (pintype "passive"))
    )
    (net (code "62") (name "Net-(U$21-PadP$1)") (class "Default")
      (node (ref "U$21") (pin "P$1") (pinfunction "P$1_P$1") (pintype "passive"))
      (node (ref "U$21") (pin "P$2") (pinfunction "P$2_P$2") (pintype "passive"))
      (node (ref "U$21") (pin "P$3") (pinfunction "P$3_P$3") (pintype "passive"))
    )
    (net (code "63") (name "Net-(U$22-PadP$1)") (class "Default")
      (node (ref "U$22") (pin "P$1") (pinfunction "P$1_P$1") (pintype "passive"))
      (node (ref "U$22") (pin "P$2") (pinfunction "P$2_P$2") (pintype "passive"))
      (node (ref "U$22") (pin "P$3") (pinfunction "P$3_P$3") (pintype "passive"))
    )
    (net (code "64") (name "Net-(U$34-PadP$1)") (class "Default")
      (node (ref "U$34") (pin "P$1") (pinfunction "P$1_P$1") (pintype "passive"))
      (node (ref "U$34") (pin "P$2") (pinfunction "P$2_P$2") (pintype "passive"))
      (node (ref "U$34") (pin "P$3") (pinfunction "P$3_P$3") (pintype "passive"))
    )
    (net (code "65") (name "Net-(U$35-PadP$2)") (class "Default")
      (node (ref "U$35") (pin "P$2") (pinfunction "P$2_P$2") (pintype "passive"))
      (node (ref "U$35") (pin "P$3") (pinfunction "P$3_P$3") (pintype "passive"))
      (node (ref "U$35") (pin "P$4") (pinfunction "P$4_P$4") (pintype "passive"))
    )
    (net (code "66") (name "Net-(U$36-PadP$2)") (class "Default")
      (node (ref "U$36") (pin "P$2") (pinfunction "P$2_P$2") (pintype "passive"))
      (node (ref "U$36") (pin "P$3") (pinfunction "P$3_P$3") (pintype "passive"))
      (node (ref "U$36") (pin "P$4") (pinfunction "P$4_P$4") (pintype "passive"))
    )
    (net (code "67") (name "Net-(U$37-PadP$1)") (class "Default")
      (node (ref "U$37") (pin "P$1") (pinfunction "P$1_P$1") (pintype "passive"))
      (node (ref "U$37") (pin "P$2") (pinfunction "P$2_P$2") (pintype "passive"))
      (node (ref "U$37") (pin "P$3") (pinfunction "P$3_P$3") (pintype "passive"))
    )
    (net (code "68") (name "Net-(U$64-PadP$1)") (class "Default")
      (node (ref "U$64") (pin "P$1") (pinfunction "P$1_P$1") (pintype "passive"))
      (node (ref "U$67") (pin "P$1") (pinfunction "P$1_P$1") (pintype "passive"))
      (node (ref "U$68") (pin "P$1") (pinfunction "P$1_P$1") (pintype "passive"))
    )
    (net (code "69") (name "Net-(U$64-PadP$2)") (class "Default")
      (node (ref "U$64") (pin "P$2") (pinfunction "P$2_P$2") (pintype "passive"))
      (node (ref "U$67") (pin "P$2") (pinfunction "P$2_P$2") (pintype "passive"))
      (node (ref "U$68") (pin "P$2") (pinfunction "P$2_P$2") (pintype "passive"))
    )
    (net (code "70") (name "Net-(U$64-PadP$3)") (class "Default")
      (node (ref "U$64") (pin "P$3") (pinfunction "P$3_P$3") (pintype "passive"))
      (node (ref "U$67") (pin "P$3") (pinfunction "P$3_P$3") (pintype "passive"))
      (node (ref "U$68") (pin "P$3") (pinfunction "P$3_P$3") (pintype "passive"))
    )
    (net (code "71") (name "Net-(U$64-PadP$4)") (class "Default")
      (node (ref "U$64") (pin "P$4") (pinfunction "P$4_P$4") (pintype "passive"))
      (node (ref "U$67") (pin "P$4") (pinfunction "P$4_P$4") (pintype "passive"))
      (node (ref "U$68") (pin "P$4") (pinfunction "P$4_P$4") (pintype "passive"))
    )
    (net (code "72") (name "Net-(U$65-PadP$1)") (class "Default")
      (node (ref "U$65") (pin "P$1") (pinfunction "P$1_P$1") (pintype "passive"))
      (node (ref "U$66") (pin "P$1") (pinfunction "P$1_P$1") (pintype "passive"))
      (node (ref "U$69") (pin "P$1") (pinfunction "P$1_P$1") (pintype "passive"))
    )
    (net (code "73") (name "Net-(U$65-PadP$2)") (class "Default")
      (node (ref "U$65") (pin "P$2") (pinfunction "P$2_P$2") (pintype "passive"))
      (node (ref "U$66") (pin "P$2") (pinfunction "P$2_P$2") (pintype "passive"))
      (node (ref "U$69") (pin "P$2") (pinfunction "P$2_P$2") (pintype "passive"))
    )
    (net (code "74") (name "Net-(U$65-PadP$3)") (class "Default")
      (node (ref "U$65") (pin "P$3") (pinfunction "P$3_P$3") (pintype "passive"))
      (node (ref "U$66") (pin "P$3") (pinfunction "P$3_P$3") (pintype "passive"))
      (node (ref "U$69") (pin "P$3") (pinfunction "P$3_P$3") (pintype "passive"))
    )
    (net (code "75") (name "Net-(U$65-PadP$4)") (class "Default")
      (node (ref "U$65") (pin "P$4") (pinfunction "P$4_P$4") (pintype "passive"))
      (node (ref "U$66") (pin "P$4") (pinfunction "P$4_P$4") (pintype "passive"))
      (node (ref "U$69") (pin "P$4") (pinfunction "P$4_P$4") (pintype "passive"))
    )
    (net (code "76") (name "Net-(U$76-PadP$1)") (class "Default")
      (node (ref "U$76") (pin "P$1") (pinfunction "P$1_P$1") (pintype "passive"))
      (node (ref "U$76") (pin "P$2") (pinfunction "P$2_P$2") (pintype "passive"))
      (node (ref "U$76") (pin "P$3") (pinfunction "P$3_P$3") (pintype "passive"))
    )
    (net (code "77") (name "Net-(U$81-PadP$1)") (class "Default")
      (node (ref "U$81") (pin "P$1") (pinfunction "P$1_P$1") (pintype "passive"))
      (node (ref "U$81") (pin "P$2") (pinfunction "P$2_P$2") (pintype "passive"))
      (node (ref "U$81") (pin "P$3") (pinfunction "P$3_P$3") (pintype "passive"))
    )
    (net (code "78") (name "Net-(U$88-PadP$1)") (class "Default")
      (node (ref "U$88") (pin "P$1") (pinfunction "P$1_P$1") (pintype "passive"))
      (node (ref "U$88") (pin "P$2") (pinfunction "P$2_P$2") (pintype "passive"))
      (node (ref "U$88") (pin "P$3") (pinfunction "P$3_P$3") (pintype "passive"))
    )
    (net (code "79") (name "Net-(U$89-PadP$1)") (class "Default")
      (node (ref "U$89") (pin "P$1") (pinfunction "P$1_P$1") (pintype "passive"))
      (node (ref "U$89") (pin "P$2") (pinfunction "P$2_P$2") (pintype "passive"))
      (node (ref "U$89") (pin "P$3") (pinfunction "P$3_P$3") (pintype "passive"))
    )
    (net (code "80") (name "Net-(U$96-PadP$1)") (class "Default")
      (node (ref "U$96") (pin "P$1") (pinfunction "P$1_P$1") (pintype "passive"))
      (node (ref "U$96") (pin "P$2") (pinfunction "P$2_P$2") (pintype "passive"))
      (node (ref "U$96") (pin "P$3") (pinfunction "P$3_P$3") (pintype "passive"))
    )
    (net (code "81") (name "Net-(U$99-PadP$1)") (class "Default")
      (node (ref "U$99") (pin "P$1") (pinfunction "P$1_P$1") (pintype "passive"))
      (node (ref "U$99") (pin "P$2") (pinfunction "P$2_P$2") (pintype "passive"))
      (node (ref "U$99") (pin "P$3") (pinfunction "P$3_P$3") (pintype "passive"))
    )
    (net (code "82") (name "V+") (class "Default")
      (node (ref "U$1") (pin "IVIN") (pinfunction "VIN_IVIN") (pintype "power_in"))
      (node (ref "U$1") (pin "OVIN") (pinfunction "VIN_OVIN") (pintype "power_in"))
      (node (ref "U$33") (pin "P$1") (pinfunction "P$1_P$1") (pintype "passive"))
    )
    (net (code "83") (name "unconnected-(U$1C-13-PadO1.13)") (class "Default")
      (node (ref "U$1") (pin "O1.13") (pinfunction "13_O1.13") (pintype "passive"))
    )
    (net (code "84") (name "unconnected-(U$1C-14-PadO1.14)") (class "Default")
      (node (ref "U$1") (pin "O1.14") (pinfunction "14_O1.14") (pintype "passive"))
    )
    (net (code "85") (name "unconnected-(U$1C-15-PadO1.15)") (class "Default")
      (node (ref "U$1") (pin "O1.15") (pinfunction "15_O1.15") (pintype "passive"))
    )
    (net (code "86") (name "unconnected-(U$1C-16-PadO1.16)") (class "Default")
      (node (ref "U$1") (pin "O1.16") (pinfunction "16_O1.16") (pintype "passive"))
    )
    (net (code "87") (name "unconnected-(U$1D-13-PadO2.13)") (class "Default")
      (node (ref "U$1") (pin "O2.13") (pinfunction "13_O2.13") (pintype "passive"))
    )
    (net (code "88") (name "unconnected-(U$1D-14-PadO2.14)") (class "Default")
      (node (ref "U$1") (pin "O2.14") (pinfunction "14_O2.14") (pintype "passive"))
    )
    (net (code "89") (name "unconnected-(U$1D-15-PadO2.15)") (class "Default")
      (node (ref "U$1") (pin "O2.15") (pinfunction "15_O2.15") (pintype "passive"))
    )
    (net (code "90") (name "unconnected-(U$1D-16-PadO2.16)") (class "Default")
      (node (ref "U$1") (pin "O2.16") (pinfunction "16_O2.16") (pintype "passive"))
    )
    (net (code "91") (name "unconnected-(U$38-PadP$1)") (class "Default")
      (node (ref "U$38") (pin "P$1") (pinfunction "P$1_P$1") (pintype "passive"))
    )
    (net (code "92") (name "unconnected-(U$38-PadP$2)") (class "Default")
      (node (ref "U$38") (pin "P$2") (pinfunction "P$2_P$2") (pintype "passive"))
    )
    (net (code "93") (name "unconnected-(U$38-PadP$3)") (class "Default")
      (node (ref "U$38") (pin "P$3") (pinfunction "P$3_P$3") (pintype "passive"))
    )
    (net (code "94") (name "unconnected-(U$38-PadP$4)") (class "Default")
      (node (ref "U$38") (pin "P$4") (pinfunction "P$4_P$4") (pintype "passive"))
    )
    (net (code "95") (name "unconnected-(U$39-PadP$1)") (class "Default")
      (node (ref "U$39") (pin "P$1") (pinfunction "P$1_P$1") (pintype "passive"))
    )
    (net (code "96") (name "unconnected-(U$39-PadP$2)") (class "Default")
      (node (ref "U$39") (pin "P$2") (pinfunction "P$2_P$2") (pintype "passive"))
    )
    (net (code "97") (name "unconnected-(U$39-PadP$3)") (class "Default")
      (node (ref "U$39") (pin "P$3") (pinfunction "P$3_P$3") (pintype "passive"))
    )
    (net (code "98") (name "unconnected-(U$39-PadP$4)") (class "Default")
      (node (ref "U$39") (pin "P$4") (pinfunction "P$4_P$4") (pintype "passive"))
    )
    (net (code "99") (name "unconnected-(U$40-PadP$1)") (class "Default")
      (node (ref "U$40") (pin "P$1") (pinfunction "P$1_P$1") (pintype "passive"))
    )
    (net (code "100") (name "unconnected-(U$40-PadP$2)") (class "Default")
      (node (ref "U$40") (pin "P$2") (pinfunction "P$2_P$2") (pintype "passive"))
    )
    (net (code "101") (name "unconnected-(U$40-PadP$3)") (class "Default")
      (node (ref "U$40") (pin "P$3") (pinfunction "P$3_P$3") (pintype "passive"))
    )
    (net (code "102") (name "unconnected-(U$40-PadP$4)") (class "Default")
      (node (ref "U$40") (pin "P$4") (pinfunction "P$4_P$4") (pintype "passive"))
    )
    (net (code "103") (name "unconnected-(U$41-PadP$1)") (class "Default")
      (node (ref "U$41") (pin "P$1") (pinfunction "P$1_P$1") (pintype "passive"))
    )
    (net (code "104") (name "unconnected-(U$41-PadP$2)") (class "Default")
      (node (ref "U$41") (pin "P$2") (pinfunction "P$2_P$2") (pintype "passive"))
    )
    (net (code "105") (name "unconnected-(U$41-PadP$3)") (class "Default")
      (node (ref "U$41") (pin "P$3") (pinfunction "P$3_P$3") (pintype "passive"))
    )
    (net (code "106") (name "unconnected-(U$41-PadP$4)") (class "Default")
      (node (ref "U$41") (pin "P$4") (pinfunction "P$4_P$4") (pintype "passive"))
    )
    (net (code "107") (name "unconnected-(U$42-PadP$1)") (class "Default")
      (node (ref "U$42") (pin "P$1") (pinfunction "P$1_P$1") (pintype "passive"))
    )
    (net (code "108") (name "unconnected-(U$42-PadP$2)") (class "Default")
      (node (ref "U$42") (pin "P$2") (pinfunction "P$2_P$2") (pintype "passive"))
    )
    (net (code "109") (name "unconnected-(U$42-PadP$3)") (class "Default")
      (node (ref "U$42") (pin "P$3") (pinfunction "P$3_P$3") (pintype "passive"))
    )
    (net (code "110") (name "unconnected-(U$42-PadP$4)") (class "Default")
      (node (ref "U$42") (pin "P$4") (pinfunction "P$4_P$4") (pintype "passive"))
    )
    (net (code "111") (name "unconnected-(U$43-PadP$1)") (class "Default")
      (node (ref "U$43") (pin "P$1") (pinfunction "P$1_P$1") (pintype "passive"))
    )
    (net (code "112") (name "unconnected-(U$43-PadP$2)") (class "Default")
      (node (ref "U$43") (pin "P$2") (pinfunction "P$2_P$2") (pintype "passive"))
    )
    (net (code "113") (name "unconnected-(U$43-PadP$3)") (class "Default")
      (node (ref "U$43") (pin "P$3") (pinfunction "P$3_P$3") (pintype "passive"))
    )
    (net (code "114") (name "unconnected-(U$43-PadP$4)") (class "Default")
      (node (ref "U$43") (pin "P$4") (pinfunction "P$4_P$4") (pintype "passive"))
    )
    (net (code "115") (name "unconnected-(U$44-PadP$1)") (class "Default")
      (node (ref "U$44") (pin "P$1") (pinfunction "P$1_P$1") (pintype "passive"))
    )
    (net (code "116") (name "unconnected-(U$44-PadP$2)") (class "Default")
      (node (ref "U$44") (pin "P$2") (pinfunction "P$2_P$2") (pintype "passive"))
    )
    (net (code "117") (name "unconnected-(U$44-PadP$3)") (class "Default")
      (node (ref "U$44") (pin "P$3") (pinfunction "P$3_P$3") (pintype "passive"))
    )
    (net (code "118") (name "unconnected-(U$44-PadP$4)") (class "Default")
      (node (ref "U$44") (pin "P$4") (pinfunction "P$4_P$4") (pintype "passive"))
    )
    (net (code "119") (name "unconnected-(U$45-PadP$1)") (class "Default")
      (node (ref "U$45") (pin "P$1") (pinfunction "P$1_P$1") (pintype "passive"))
    )
    (net (code "120") (name "unconnected-(U$45-PadP$2)") (class "Default")
      (node (ref "U$45") (pin "P$2") (pinfunction "P$2_P$2") (pintype "passive"))
    )
    (net (code "121") (name "unconnected-(U$45-PadP$3)") (class "Default")
      (node (ref "U$45") (pin "P$3") (pinfunction "P$3_P$3") (pintype "passive"))
    )
    (net (code "122") (name "unconnected-(U$45-PadP$4)") (class "Default")
      (node (ref "U$45") (pin "P$4") (pinfunction "P$4_P$4") (pintype "passive"))
    )
    (net (code "123") (name "unconnected-(U$46-PadP$1)") (class "Default")
      (node (ref "U$46") (pin "P$1") (pinfunction "P$1_P$1") (pintype "passive"))
    )
    (net (code "124") (name "unconnected-(U$46-PadP$2)") (class "Default")
      (node (ref "U$46") (pin "P$2") (pinfunction "P$2_P$2") (pintype "passive"))
    )
    (net (code "125") (name "unconnected-(U$46-PadP$3)") (class "Default")
      (node (ref "U$46") (pin "P$3") (pinfunction "P$3_P$3") (pintype "passive"))
    )
    (net (code "126") (name "unconnected-(U$46-PadP$4)") (class "Default")
      (node (ref "U$46") (pin "P$4") (pinfunction "P$4_P$4") (pintype "passive"))
    )
    (net (code "127") (name "unconnected-(U$47-PadP$1)") (class "Default")
      (node (ref "U$47") (pin "P$1") (pinfunction "P$1_P$1") (pintype "passive"))
    )
    (net (code "128") (name "unconnected-(U$47-PadP$2)") (class "Default")
      (node (ref "U$47") (pin "P$2") (pinfunction "P$2_P$2") (pintype "passive"))
    )
    (net (code "129") (name "unconnected-(U$47-PadP$3)") (class "Default")
      (node (ref "U$47") (pin "P$3") (pinfunction "P$3_P$3") (pintype "passive"))
    )
    (net (code "130") (name "unconnected-(U$47-PadP$4)") (class "Default")
      (node (ref "U$47") (pin "P$4") (pinfunction "P$4_P$4") (pintype "passive"))
    )
    (net (code "131") (name "unconnected-(U$48-PadP$1)") (class "Default")
      (node (ref "U$48") (pin "P$1") (pinfunction "P$1_P$1") (pintype "passive"))
    )
    (net (code "132") (name "unconnected-(U$48-PadP$2)") (class "Default")
      (node (ref "U$48") (pin "P$2") (pinfunction "P$2_P$2") (pintype "passive"))
    )
    (net (code "133") (name "unconnected-(U$48-PadP$3)") (class "Default")
      (node (ref "U$48") (pin "P$3") (pinfunction "P$3_P$3") (pintype "passive"))
    )
    (net (code "134") (name "unconnected-(U$48-PadP$4)") (class "Default")
      (node (ref "U$48") (pin "P$4") (pinfunction "P$4_P$4") (pintype "passive"))
    )
    (net (code "135") (name "unconnected-(U$49-PadP$1)") (class "Default")
      (node (ref "U$49") (pin "P$1") (pinfunction "P$1_P$1") (pintype "passive"))
    )
    (net (code "136") (name "unconnected-(U$49-PadP$2)") (class "Default")
      (node (ref "U$49") (pin "P$2") (pinfunction "P$2_P$2") (pintype "passive"))
    )
    (net (code "137") (name "unconnected-(U$49-PadP$3)") (class "Default")
      (node (ref "U$49") (pin "P$3") (pinfunction "P$3_P$3") (pintype "passive"))
    )
    (net (code "138") (name "unconnected-(U$49-PadP$4)") (class "Default")
      (node (ref "U$49") (pin "P$4") (pinfunction "P$4_P$4") (pintype "passive"))
    )
    (net (code "139") (name "unconnected-(U$50-PadP$1)") (class "Default")
      (node (ref "U$50") (pin "P$1") (pinfunction "P$1_P$1") (pintype "passive"))
    )
    (net (code "140") (name "unconnected-(U$50-PadP$2)") (class "Default")
      (node (ref "U$50") (pin "P$2") (pinfunction "P$2_P$2") (pintype "passive"))
    )
    (net (code "141") (name "unconnected-(U$50-PadP$3)") (class "Default")
      (node (ref "U$50") (pin "P$3") (pinfunction "P$3_P$3") (pintype "passive"))
    )
    (net (code "142") (name "unconnected-(U$50-PadP$4)") (class "Default")
      (node (ref "U$50") (pin "P$4") (pinfunction "P$4_P$4") (pintype "passive"))
    )
    (net (code "143") (name "unconnected-(U$51-PadP$1)") (class "Default")
      (node (ref "U$51") (pin "P$1") (pinfunction "P$1_P$1") (pintype "passive"))
    )
    (net (code "144") (name "unconnected-(U$51-PadP$2)") (class "Default")
      (node (ref "U$51") (pin "P$2") (pinfunction "P$2_P$2") (pintype "passive"))
    )
    (net (code "145") (name "unconnected-(U$51-PadP$3)") (class "Default")
      (node (ref "U$51") (pin "P$3") (pinfunction "P$3_P$3") (pintype "passive"))
    )
    (net (code "146") (name "unconnected-(U$51-PadP$4)") (class "Default")
      (node (ref "U$51") (pin "P$4") (pinfunction "P$4_P$4") (pintype "passive"))
    )
    (net (code "147") (name "unconnected-(U$52-PadP$1)") (class "Default")
      (node (ref "U$52") (pin "P$1") (pinfunction "P$1_P$1") (pintype "passive"))
    )
    (net (code "148") (name "unconnected-(U$52-PadP$2)") (class "Default")
      (node (ref "U$52") (pin "P$2") (pinfunction "P$2_P$2") (pintype "passive"))
    )
    (net (code "149") (name "unconnected-(U$52-PadP$3)") (class "Default")
      (node (ref "U$52") (pin "P$3") (pinfunction "P$3_P$3") (pintype "passive"))
    )
    (net (code "150") (name "unconnected-(U$52-PadP$4)") (class "Default")
      (node (ref "U$52") (pin "P$4") (pinfunction "P$4_P$4") (pintype "passive"))
    )
    (net (code "151") (name "unconnected-(U$53-PadP$1)") (class "Default")
      (node (ref "U$53") (pin "P$1") (pinfunction "P$1_P$1") (pintype "passive"))
    )
    (net (code "152") (name "unconnected-(U$53-PadP$2)") (class "Default")
      (node (ref "U$53") (pin "P$2") (pinfunction "P$2_P$2") (pintype "passive"))
    )
    (net (code "153") (name "unconnected-(U$53-PadP$3)") (class "Default")
      (node (ref "U$53") (pin "P$3") (pinfunction "P$3_P$3") (pintype "passive"))
    )
    (net (code "154") (name "unconnected-(U$53-PadP$4)") (class "Default")
      (node (ref "U$53") (pin "P$4") (pinfunction "P$4_P$4") (pintype "passive"))
    )
    (net (code "155") (name "unconnected-(U$54-PadP$1)") (class "Default")
      (node (ref "U$54") (pin "P$1") (pinfunction "P$1_P$1") (pintype "passive"))
    )
    (net (code "156") (name "unconnected-(U$54-PadP$2)") (class "Default")
      (node (ref "U$54") (pin "P$2") (pinfunction "P$2_P$2") (pintype "passive"))
    )
    (net (code "157") (name "unconnected-(U$54-PadP$3)") (class "Default")
      (node (ref "U$54") (pin "P$3") (pinfunction "P$3_P$3") (pintype "passive"))
    )
    (net (code "158") (name "unconnected-(U$54-PadP$4)") (class "Default")
      (node (ref "U$54") (pin "P$4") (pinfunction "P$4_P$4") (pintype "passive"))
    )
    (net (code "159") (name "unconnected-(U$55-PadP$1)") (class "Default")
      (node (ref "U$55") (pin "P$1") (pinfunction "P$1_P$1") (pintype "passive"))
    )
    (net (code "160") (name "unconnected-(U$55-PadP$2)") (class "Default")
      (node (ref "U$55") (pin "P$2") (pinfunction "P$2_P$2") (pintype "passive"))
    )
    (net (code "161") (name "unconnected-(U$55-PadP$3)") (class "Default")
      (node (ref "U$55") (pin "P$3") (pinfunction "P$3_P$3") (pintype "passive"))
    )
    (net (code "162") (name "unconnected-(U$55-PadP$4)") (class "Default")
      (node (ref "U$55") (pin "P$4") (pinfunction "P$4_P$4") (pintype "passive"))
    )
    (net (code "163") (name "unconnected-(U$56-PadP$1)") (class "Default")
      (node (ref "U$56") (pin "P$1") (pinfunction "P$1_P$1") (pintype "passive"))
    )
    (net (code "164") (name "unconnected-(U$56-PadP$2)") (class "Default")
      (node (ref "U$56") (pin "P$2") (pinfunction "P$2_P$2") (pintype "passive"))
    )
    (net (code "165") (name "unconnected-(U$56-PadP$3)") (class "Default")
      (node (ref "U$56") (pin "P$3") (pinfunction "P$3_P$3") (pintype "passive"))
    )
    (net (code "166") (name "unconnected-(U$56-PadP$4)") (class "Default")
      (node (ref "U$56") (pin "P$4") (pinfunction "P$4_P$4") (pintype "passive"))
    )
    (net (code "167") (name "unconnected-(U$57-PadP$1)") (class "Default")
      (node (ref "U$57") (pin "P$1") (pinfunction "P$1_P$1") (pintype "passive"))
    )
    (net (code "168") (name "unconnected-(U$57-PadP$2)") (class "Default")
      (node (ref "U$57") (pin "P$2") (pinfunction "P$2_P$2") (pintype "passive"))
    )
    (net (code "169") (name "unconnected-(U$57-PadP$3)") (class "Default")
      (node (ref "U$57") (pin "P$3") (pinfunction "P$3_P$3") (pintype "passive"))
    )
    (net (code "170") (name "unconnected-(U$57-PadP$4)") (class "Default")
      (node (ref "U$57") (pin "P$4") (pinfunction "P$4_P$4") (pintype "passive"))
    )
    (net (code "171") (name "unconnected-(U$58-PadP$1)") (class "Default")
      (node (ref "U$58") (pin "P$1") (pinfunction "P$1_P$1") (pintype "passive"))
    )
    (net (code "172") (name "unconnected-(U$58-PadP$2)") (class "Default")
      (node (ref "U$58") (pin "P$2") (pinfunction "P$2_P$2") (pintype "passive"))
    )
    (net (code "173") (name "unconnected-(U$58-PadP$3)") (class "Default")
      (node (ref "U$58") (pin "P$3") (pinfunction "P$3_P$3") (pintype "passive"))
    )
    (net (code "174") (name "unconnected-(U$58-PadP$4)") (class "Default")
      (node (ref "U$58") (pin "P$4") (pinfunction "P$4_P$4") (pintype "passive"))
    )
    (net (code "175") (name "unconnected-(U$59-PadP$1)") (class "Default")
      (node (ref "U$59") (pin "P$1") (pinfunction "P$1_P$1") (pintype "passive"))
    )
    (net (code "176") (name "unconnected-(U$59-PadP$2)") (class "Default")
      (node (ref "U$59") (pin "P$2") (pinfunction "P$2_P$2") (pintype "passive"))
    )
    (net (code "177") (name "unconnected-(U$59-PadP$3)") (class "Default")
      (node (ref "U$59") (pin "P$3") (pinfunction "P$3_P$3") (pintype "passive"))
    )
    (net (code "178") (name "unconnected-(U$59-PadP$4)") (class "Default")
      (node (ref "U$59") (pin "P$4") (pinfunction "P$4_P$4") (pintype "passive"))
    )
    (net (code "179") (name "unconnected-(U$60-PadP$1)") (class "Default")
      (node (ref "U$60") (pin "P$1") (pinfunction "P$1_P$1") (pintype "passive"))
    )
    (net (code "180") (name "unconnected-(U$60-PadP$2)") (class "Default")
      (node (ref "U$60") (pin "P$2") (pinfunction "P$2_P$2") (pintype "passive"))
    )
    (net (code "181") (name "unconnected-(U$60-PadP$3)") (class "Default")
      (node (ref "U$60") (pin "P$3") (pinfunction "P$3_P$3") (pintype "passive"))
    )
    (net (code "182") (name "unconnected-(U$60-PadP$4)") (class "Default")
      (node (ref "U$60") (pin "P$4") (pinfunction "P$4_P$4") (pintype "passive"))
    )
    (net (code "183") (name "unconnected-(U$61-PadP$1)") (class "Default")
      (node (ref "U$61") (pin "P$1") (pinfunction "P$1_P$1") (pintype "passive"))
    )
    (net (code "184") (name "unconnected-(U$61-PadP$2)") (class "Default")
      (node (ref "U$61") (pin "P$2") (pinfunction "P$2_P$2") (pintype "passive"))
    )
    (net (code "185") (name "unconnected-(U$61-PadP$3)") (class "Default")
      (node (ref "U$61") (pin "P$3") (pinfunction "P$3_P$3") (pintype "passive"))
    )
    (net (code "186") (name "unconnected-(U$61-PadP$4)") (class "Default")
      (node (ref "U$61") (pin "P$4") (pinfunction "P$4_P$4") (pintype "passive"))
    )
    (net (code "187") (name "unconnected-(U$62-PadP$1)") (class "Default")
      (node (ref "U$62") (pin "P$1") (pinfunction "P$1_P$1") (pintype "passive"))
    )
    (net (code "188") (name "unconnected-(U$62-PadP$2)") (class "Default")
      (node (ref "U$62") (pin "P$2") (pinfunction "P$2_P$2") (pintype "passive"))
    )
    (net (code "189") (name "unconnected-(U$62-PadP$3)") (class "Default")
      (node (ref "U$62") (pin "P$3") (pinfunction "P$3_P$3") (pintype "passive"))
    )
    (net (code "190") (name "unconnected-(U$62-PadP$4)") (class "Default")
      (node (ref "U$62") (pin "P$4") (pinfunction "P$4_P$4") (pintype "passive"))
    )
    (net (code "191") (name "unconnected-(U$63-PadP$1)") (class "Default")
      (node (ref "U$63") (pin "P$1") (pinfunction "P$1_P$1") (pintype "passive"))
    )
    (net (code "192") (name "unconnected-(U$63-PadP$2)") (class "Default")
      (node (ref "U$63") (pin "P$2") (pinfunction "P$2_P$2") (pintype "passive"))
    )
    (net (code "193") (name "unconnected-(U$63-PadP$3)") (class "Default")
      (node (ref "U$63") (pin "P$3") (pinfunction "P$3_P$3") (pintype "passive"))
    )
    (net (code "194") (name "unconnected-(U$63-PadP$4)") (class "Default")
      (node (ref "U$63") (pin "P$4") (pinfunction "P$4_P$4") (pintype "passive"))
    )
    (net (code "195") (name "unconnected-(U$70-PadP$1)") (class "Default")
      (node (ref "U$70") (pin "P$1") (pinfunction "P$1_P$1") (pintype "passive"))
    )
    (net (code "196") (name "unconnected-(U$70-PadP$2)") (class "Default")
      (node (ref "U$70") (pin "P$2") (pinfunction "P$2_P$2") (pintype "passive"))
    )
    (net (code "197") (name "unconnected-(U$70-PadP$3)") (class "Default")
      (node (ref "U$70") (pin "P$3") (pinfunction "P$3_P$3") (pintype "passive"))
    )
    (net (code "198") (name "unconnected-(U$70-PadP$4)") (class "Default")
      (node (ref "U$70") (pin "P$4") (pinfunction "P$4_P$4") (pintype "passive"))
    )
    (net (code "199") (name "unconnected-(U$71-PadP$1)") (class "Default")
      (node (ref "U$71") (pin "P$1") (pinfunction "P$1_P$1") (pintype "passive"))
    )
    (net (code "200") (name "unconnected-(U$71-PadP$2)") (class "Default")
      (node (ref "U$71") (pin "P$2") (pinfunction "P$2_P$2") (pintype "passive"))
    )
    (net (code "201") (name "unconnected-(U$71-PadP$3)") (class "Default")
      (node (ref "U$71") (pin "P$3") (pinfunction "P$3_P$3") (pintype "passive"))
    )
    (net (code "202") (name "unconnected-(U$71-PadP$4)") (class "Default")
      (node (ref "U$71") (pin "P$4") (pinfunction "P$4_P$4") (pintype "passive"))
    )
    (net (code "203") (name "unconnected-(U$72-PadP$1)") (class "Default")
      (node (ref "U$72") (pin "P$1") (pinfunction "P$1_P$1") (pintype "passive"))
    )
    (net (code "204") (name "unconnected-(U$72-PadP$2)") (class "Default")
      (node (ref "U$72") (pin "P$2") (pinfunction "P$2_P$2") (pintype "passive"))
    )
    (net (code "205") (name "unconnected-(U$72-PadP$3)") (class "Default")
      (node (ref "U$72") (pin "P$3") (pinfunction "P$3_P$3") (pintype "passive"))
    )
    (net (code "206") (name "unconnected-(U$72-PadP$4)") (class "Default")
      (node (ref "U$72") (pin "P$4") (pinfunction "P$4_P$4") (pintype "passive"))
    )
    (net (code "207") (name "unconnected-(U$73-PadP$1)") (class "Default")
      (node (ref "U$73") (pin "P$1") (pinfunction "P$1_P$1") (pintype "passive"))
    )
    (net (code "208") (name "unconnected-(U$73-PadP$2)") (class "Default")
      (node (ref "U$73") (pin "P$2") (pinfunction "P$2_P$2") (pintype "passive"))
    )
    (net (code "209") (name "unconnected-(U$73-PadP$3)") (class "Default")
      (node (ref "U$73") (pin "P$3") (pinfunction "P$3_P$3") (pintype "passive"))
    )
    (net (code "210") (name "unconnected-(U$73-PadP$4)") (class "Default")
      (node (ref "U$73") (pin "P$4") (pinfunction "P$4_P$4") (pintype "passive"))
    )
    (net (code "211") (name "unconnected-(U$74-PadP$1)") (class "Default")
      (node (ref "U$74") (pin "P$1") (pinfunction "P$1_P$1") (pintype "passive"))
    )
    (net (code "212") (name "unconnected-(U$74-PadP$2)") (class "Default")
      (node (ref "U$74") (pin "P$2") (pinfunction "P$2_P$2") (pintype "passive"))
    )
    (net (code "213") (name "unconnected-(U$74-PadP$3)") (class "Default")
      (node (ref "U$74") (pin "P$3") (pinfunction "P$3_P$3") (pintype "passive"))
    )
    (net (code "214") (name "unconnected-(U$74-PadP$4)") (class "Default")
      (node (ref "U$74") (pin "P$4") (pinfunction "P$4_P$4") (pintype "passive"))
    )
    (net (code "215") (name "unconnected-(U$75-PadP$1)") (class "Default")
      (node (ref "U$75") (pin "P$1") (pinfunction "P$1_P$1") (pintype "passive"))
    )
    (net (code "216") (name "unconnected-(U$75-PadP$2)") (class "Default")
      (node (ref "U$75") (pin "P$2") (pinfunction "P$2_P$2") (pintype "passive"))
    )
    (net (code "217") (name "unconnected-(U$75-PadP$3)") (class "Default")
      (node (ref "U$75") (pin "P$3") (pinfunction "P$3_P$3") (pintype "passive"))
    )
    (net (code "218") (name "unconnected-(U$75-PadP$4)") (class "Default")
      (node (ref "U$75") (pin "P$4") (pinfunction "P$4_P$4") (pintype "passive"))
    )
    (net (code "219") (name "unconnected-(U$76-PadP$4)") (class "Default")
      (node (ref "U$76") (pin "P$4") (pinfunction "P$4_P$4") (pintype "passive"))
    )
    (net (code "220") (name "unconnected-(U$81-PadP$4)") (class "Default")
      (node (ref "U$81") (pin "P$4") (pinfunction "P$4_P$4") (pintype "passive"))
    )
    (net (code "221") (name "unconnected-(U$82-PadP$1)") (class "Default")
      (node (ref "U$82") (pin "P$1") (pinfunction "P$1_P$1") (pintype "passive"))
    )
    (net (code "222") (name "unconnected-(U$82-PadP$2)") (class "Default")
      (node (ref "U$82") (pin "P$2") (pinfunction "P$2_P$2") (pintype "passive"))
    )
    (net (code "223") (name "unconnected-(U$82-PadP$3)") (class "Default")
      (node (ref "U$82") (pin "P$3") (pinfunction "P$3_P$3") (pintype "passive"))
    )
    (net (code "224") (name "unconnected-(U$82-PadP$4)") (class "Default")
      (node (ref "U$82") (pin "P$4") (pinfunction "P$4_P$4") (pintype "passive"))
    )
    (net (code "225") (name "unconnected-(U$83-PadP$1)") (class "Default")
      (node (ref "U$83") (pin "P$1") (pinfunction "P$1_P$1") (pintype "passive"))
    )
    (net (code "226") (name "unconnected-(U$83-PadP$2)") (class "Default")
      (node (ref "U$83") (pin "P$2") (pinfunction "P$2_P$2") (pintype "passive"))
    )
    (net (code "227") (name "unconnected-(U$83-PadP$3)") (class "Default")
      (node (ref "U$83") (pin "P$3") (pinfunction "P$3_P$3") (pintype "passive"))
    )
    (net (code "228") (name "unconnected-(U$83-PadP$4)") (class "Default")
      (node (ref "U$83") (pin "P$4") (pinfunction "P$4_P$4") (pintype "passive"))
    )
    (net (code "229") (name "unconnected-(U$84-PadP$1)") (class "Default")
      (node (ref "U$84") (pin "P$1") (pinfunction "P$1_P$1") (pintype "passive"))
    )
    (net (code "230") (name "unconnected-(U$84-PadP$2)") (class "Default")
      (node (ref "U$84") (pin "P$2") (pinfunction "P$2_P$2") (pintype "passive"))
    )
    (net (code "231") (name "unconnected-(U$84-PadP$3)") (class "Default")
      (node (ref "U$84") (pin "P$3") (pinfunction "P$3_P$3") (pintype "passive"))
    )
    (net (code "232") (name "unconnected-(U$84-PadP$4)") (class "Default")
      (node (ref "U$84") (pin "P$4") (pinfunction "P$4_P$4") (pintype "passive"))
    )
    (net (code "233") (name "unconnected-(U$85-PadP$1)") (class "Default")
      (node (ref "U$85") (pin "P$1") (pinfunction "P$1_P$1") (pintype "passive"))
    )
    (net (code "234") (name "unconnected-(U$85-PadP$2)") (class "Default")
      (node (ref "U$85") (pin "P$2") (pinfunction "P$2_P$2") (pintype "passive"))
    )
    (net (code "235") (name "unconnected-(U$85-PadP$3)") (class "Default")
      (node (ref "U$85") (pin "P$3") (pinfunction "P$3_P$3") (pintype "passive"))
    )
    (net (code "236") (name "unconnected-(U$85-PadP$4)") (class "Default")
      (node (ref "U$85") (pin "P$4") (pinfunction "P$4_P$4") (pintype "passive"))
    )
    (net (code "237") (name "unconnected-(U$86-PadP$1)") (class "Default")
      (node (ref "U$86") (pin "P$1") (pinfunction "P$1_P$1") (pintype "passive"))
    )
    (net (code "238") (name "unconnected-(U$86-PadP$2)") (class "Default")
      (node (ref "U$86") (pin "P$2") (pinfunction "P$2_P$2") (pintype "passive"))
    )
    (net (code "239") (name "unconnected-(U$86-PadP$3)") (class "Default")
      (node (ref "U$86") (pin "P$3") (pinfunction "P$3_P$3") (pintype "passive"))
    )
    (net (code "240") (name "unconnected-(U$86-PadP$4)") (class "Default")
      (node (ref "U$86") (pin "P$4") (pinfunction "P$4_P$4") (pintype "passive"))
    )
    (net (code "241") (name "unconnected-(U$87-PadP$1)") (class "Default")
      (node (ref "U$87") (pin "P$1") (pinfunction "P$1_P$1") (pintype "passive"))
    )
    (net (code "242") (name "unconnected-(U$87-PadP$2)") (class "Default")
      (node (ref "U$87") (pin "P$2") (pinfunction "P$2_P$2") (pintype "passive"))
    )
    (net (code "243") (name "unconnected-(U$87-PadP$3)") (class "Default")
      (node (ref "U$87") (pin "P$3") (pinfunction "P$3_P$3") (pintype "passive"))
    )
    (net (code "244") (name "unconnected-(U$87-PadP$4)") (class "Default")
      (node (ref "U$87") (pin "P$4") (pinfunction "P$4_P$4") (pintype "passive"))
    )
    (net (code "245") (name "unconnected-(U$88-PadP$4)") (class "Default")
      (node (ref "U$88") (pin "P$4") (pinfunction "P$4_P$4") (pintype "passive"))
    )
    (net (code "246") (name "unconnected-(U$89-PadP$4)") (class "Default")
      (node (ref "U$89") (pin "P$4") (pinfunction "P$4_P$4") (pintype "passive"))
    )
    (net (code "247") (name "unconnected-(U$90-PadP$1)") (class "Default")
      (node (ref "U$90") (pin "P$1") (pinfunction "P$1_P$1") (pintype "passive"))
    )
    (net (code "248") (name "unconnected-(U$90-PadP$2)") (class "Default")
      (node (ref "U$90") (pin "P$2") (pinfunction "P$2_P$2") (pintype "passive"))
    )
    (net (code "249") (name "unconnected-(U$90-PadP$3)") (class "Default")
      (node (ref "U$90") (pin "P$3") (pinfunction "P$3_P$3") (pintype "passive"))
    )
    (net (code "250") (name "unconnected-(U$90-PadP$4)") (class "Default")
      (node (ref "U$90") (pin "P$4") (pinfunction "P$4_P$4") (pintype "passive"))
    )
    (net (code "251") (name "unconnected-(U$91-PadP$1)") (class "Default")
      (node (ref "U$91") (pin "P$1") (pinfunction "P$1_P$1") (pintype "passive"))
    )
    (net (code "252") (name "unconnected-(U$91-PadP$2)") (class "Default")
      (node (ref "U$91") (pin "P$2") (pinfunction "P$2_P$2") (pintype "passive"))
    )
    (net (code "253") (name "unconnected-(U$91-PadP$3)") (class "Default")
      (node (ref "U$91") (pin "P$3") (pinfunction "P$3_P$3") (pintype "passive"))
    )
    (net (code "254") (name "unconnected-(U$91-PadP$4)") (class "Default")
      (node (ref "U$91") (pin "P$4") (pinfunction "P$4_P$4") (pintype "passive"))
    )
    (net (code "255") (name "unconnected-(U$92-PadP$1)") (class "Default")
      (node (ref "U$92") (pin "P$1") (pinfunction "P$1_P$1") (pintype "passive"))
    )
    (net (code "256") (name "unconnected-(U$92-PadP$2)") (class "Default")
      (node (ref "U$92") (pin "P$2") (pinfunction "P$2_P$2") (pintype "passive"))
    )
    (net (code "257") (name "unconnected-(U$92-PadP$3)") (class "Default")
      (node (ref "U$92") (pin "P$3") (pinfunction "P$3_P$3") (pintype "passive"))
    )
    (net (code "258") (name "unconnected-(U$92-PadP$4)") (class "Default")
      (node (ref "U$92") (pin "P$4") (pinfunction "P$4_P$4") (pintype "passive"))
    )
    (net (code "259") (name "unconnected-(U$93-PadP$1)") (class "Default")
      (node (ref "U$93") (pin "P$1") (pinfunction "P$1_P$1") (pintype "passive"))
    )
    (net (code "260") (name "unconnected-(U$93-PadP$2)") (class "Default")
      (node (ref "U$93") (pin "P$2") (pinfunction "P$2_P$2") (pintype "passive"))
    )
    (net (code "261") (name "unconnected-(U$93-PadP$3)") (class "Default")
      (node (ref "U$93") (pin "P$3") (pinfunction "P$3_P$3") (pintype "passive"))
    )
    (net (code "262") (name "unconnected-(U$93-PadP$4)") (class "Default")
      (node (ref "U$93") (pin "P$4") (pinfunction "P$4_P$4") (pintype "passive"))
    )
    (net (code "263") (name "unconnected-(U$94-PadP$1)") (class "Default")
      (node (ref "U$94") (pin "P$1") (pinfunction "P$1_P$1") (pintype "passive"))
    )
    (net (code "264") (name "unconnected-(U$94-PadP$2)") (class "Default")
      (node (ref "U$94") (pin "P$2") (pinfunction "P$2_P$2") (pintype "passive"))
    )
    (net (code "265") (name "unconnected-(U$94-PadP$3)") (class "Default")
      (node (ref "U$94") (pin "P$3") (pinfunction "P$3_P$3") (pintype "passive"))
    )
    (net (code "266") (name "unconnected-(U$94-PadP$4)") (class "Default")
      (node (ref "U$94") (pin "P$4") (pinfunction "P$4_P$4") (pintype "passive"))
    )
    (net (code "267") (name "unconnected-(U$95-PadP$1)") (class "Default")
      (node (ref "U$95") (pin "P$1") (pinfunction "P$1_P$1") (pintype "passive"))
    )
    (net (code "268") (name "unconnected-(U$95-PadP$2)") (class "Default")
      (node (ref "U$95") (pin "P$2") (pinfunction "P$2_P$2") (pintype "passive"))
    )
    (net (code "269") (name "unconnected-(U$95-PadP$3)") (class "Default")
      (node (ref "U$95") (pin "P$3") (pinfunction "P$3_P$3") (pintype "passive"))
    )
    (net (code "270") (name "unconnected-(U$95-PadP$4)") (class "Default")
      (node (ref "U$95") (pin "P$4") (pinfunction "P$4_P$4") (pintype "passive"))
    )
    (net (code "271") (name "unconnected-(U$96-PadP$4)") (class "Default")
      (node (ref "U$96") (pin "P$4") (pinfunction "P$4_P$4") (pintype "passive"))
    )
    (net (code "272") (name "unconnected-(U$97-PadP$1)") (class "Default")
      (node (ref "U$97") (pin "P$1") (pinfunction "P$1_P$1") (pintype "passive"))
    )
    (net (code "273") (name "unconnected-(U$97-PadP$2)") (class "Default")
      (node (ref "U$97") (pin "P$2") (pinfunction "P$2_P$2") (pintype "passive"))
    )
    (net (code "274") (name "unconnected-(U$97-PadP$3)") (class "Default")
      (node (ref "U$97") (pin "P$3") (pinfunction "P$3_P$3") (pintype "passive"))
    )
    (net (code "275") (name "unconnected-(U$97-PadP$4)") (class "Default")
      (node (ref "U$97") (pin "P$4") (pinfunction "P$4_P$4") (pintype "passive"))
    )
    (net (code "276") (name "unconnected-(U$98-PadP$1)") (class "Default")
      (node (ref "U$98") (pin "P$1") (pinfunction "P$1_P$1") (pintype "passive"))
    )
    (net (code "277") (name "unconnected-(U$98-PadP$2)") (class "Default")
      (node (ref "U$98") (pin "P$2") (pinfunction "P$2_P$2") (pintype "passive"))
    )
    (net (code "278") (name "unconnected-(U$98-PadP$3)") (class "Default")
      (node (ref "U$98") (pin "P$3") (pinfunction "P$3_P$3") (pintype "passive"))
    )
    (net (code "279") (name "unconnected-(U$98-PadP$4)") (class "Default")
      (node (ref "U$98") (pin "P$4") (pinfunction "P$4_P$4") (pintype "passive"))
    )
    (net (code "280") (name "unconnected-(U$99-PadP$4)") (class "Default")
      (node (ref "U$99") (pin "P$4") (pinfunction "P$4_P$4") (pintype "passive"))
    )
    (net (code "281") (name "unconnected-(U$100-PadP$1)") (class "Default")
      (node (ref "U$100") (pin "P$1") (pinfunction "P$1_P$1") (pintype "passive"))
    )
    (net (code "282") (name "unconnected-(U$100-PadP$2)") (class "Default")
      (node (ref "U$100") (pin "P$2") (pinfunction "P$2_P$2") (pintype "passive"))
    )
    (net (code "283") (name "unconnected-(U$100-PadP$3)") (class "Default")
      (node (ref "U$100") (pin "P$3") (pinfunction "P$3_P$3") (pintype "passive"))
    )
    (net (code "284") (name "unconnected-(U$100-PadP$4)") (class "Default")
      (node (ref "U$100") (pin "P$4") (pinfunction "P$4_P$4") (pintype "passive"))
    )
    (net (code "285") (name "unconnected-(U$101-PadP$1)") (class "Default")
      (node (ref "U$101") (pin "P$1") (pinfunction "P$1_P$1") (pintype "passive"))
    )
    (net (code "286") (name "unconnected-(U$101-PadP$2)") (class "Default")
      (node (ref "U$101") (pin "P$2") (pinfunction "P$2_P$2") (pintype "passive"))
    )
    (net (code "287") (name "unconnected-(U$101-PadP$3)") (class "Default")
      (node (ref "U$101") (pin "P$3") (pinfunction "P$3_P$3") (pintype "passive"))
    )
    (net (code "288") (name "unconnected-(U$101-PadP$4)") (class "Default")
      (node (ref "U$101") (pin "P$4") (pinfunction "P$4_P$4") (pintype "passive"))
    )
    (net (code "289") (name "unconnected-(U$102-PadP$1)") (class "Default")
      (node (ref "U$102") (pin "P$1") (pinfunction "P$1_P$1") (pintype "passive"))
    )
    (net (code "290") (name "unconnected-(U$102-PadP$2)") (class "Default")
      (node (ref "U$102") (pin "P$2") (pinfunction "P$2_P$2") (pintype "passive"))
    )
    (net (code "291") (name "unconnected-(U$102-PadP$3)") (class "Default")
      (node (ref "U$102") (pin "P$3") (pinfunction "P$3_P$3") (pintype "passive"))
    )
    (net (code "292") (name "unconnected-(U$102-PadP$4)") (class "Default")
      (node (ref "U$102") (pin "P$4") (pinfunction "P$4_P$4") (pintype "passive"))
    )
    (net (code "293") (name "unconnected-(U$103-PadP$1)") (class "Default")
      (node (ref "U$103") (pin "P$1") (pinfunction "P$1_P$1") (pintype "passive"))
    )
    (net (code "294") (name "unconnected-(U$103-PadP$2)") (class "Default")
      (node (ref "U$103") (pin "P$2") (pinfunction "P$2_P$2") (pintype "passive"))
    )
    (net (code "295") (name "unconnected-(U$103-PadP$3)") (class "Default")
      (node (ref "U$103") (pin "P$3") (pinfunction "P$3_P$3") (pintype "passive"))
    )
    (net (code "296") (name "unconnected-(U$103-PadP$4)") (class "Default")
      (node (ref "U$103") (pin "P$4") (pinfunction "P$4_P$4") (pintype "passive"))
    )
    (net (code "297") (name "unconnected-(U$104-PadP$1)") (class "Default")
      (node (ref "U$104") (pin "P$1") (pinfunction "P$1_P$1") (pintype "passive"))
    )
    (net (code "298") (name "unconnected-(U$104-PadP$2)") (class "Default")
      (node (ref "U$104") (pin "P$2") (pinfunction "P$2_P$2") (pintype "passive"))
    )
    (net (code "299") (name "unconnected-(U$105-PadP$1)") (class "Default")
      (node (ref "U$105") (pin "P$1") (pinfunction "P$1_P$1") (pintype "passive"))
    )
    (net (code "300") (name "unconnected-(U$105-PadP$2)") (class "Default")
      (node (ref "U$105") (pin "P$2") (pinfunction "P$2_P$2") (pintype "passive"))
    )
    (net (code "301") (name "unconnected-(U$106-PadP$1)") (class "Default")
      (node (ref "U$106") (pin "P$1") (pinfunction "P$1_P$1") (pintype "passive"))
    )
    (net (code "302") (name "unconnected-(U$106-PadP$2)") (class "Default")
      (node (ref "U$106") (pin "P$2") (pinfunction "P$2_P$2") (pintype "passive"))
    )
    (net (code "303") (name "unconnected-(U$107-PadP$1)") (class "Default")
      (node (ref "U$107") (pin "P$1") (pinfunction "P$1_P$1") (pintype "passive"))
    )
    (net (code "304") (name "unconnected-(U$107-PadP$2)") (class "Default")
      (node (ref "U$107") (pin "P$2") (pinfunction "P$2_P$2") (pintype "passive"))
    )
  )
)
